# PAM8610.net
KiCad netlist of a schematic drawn in Altium Designer
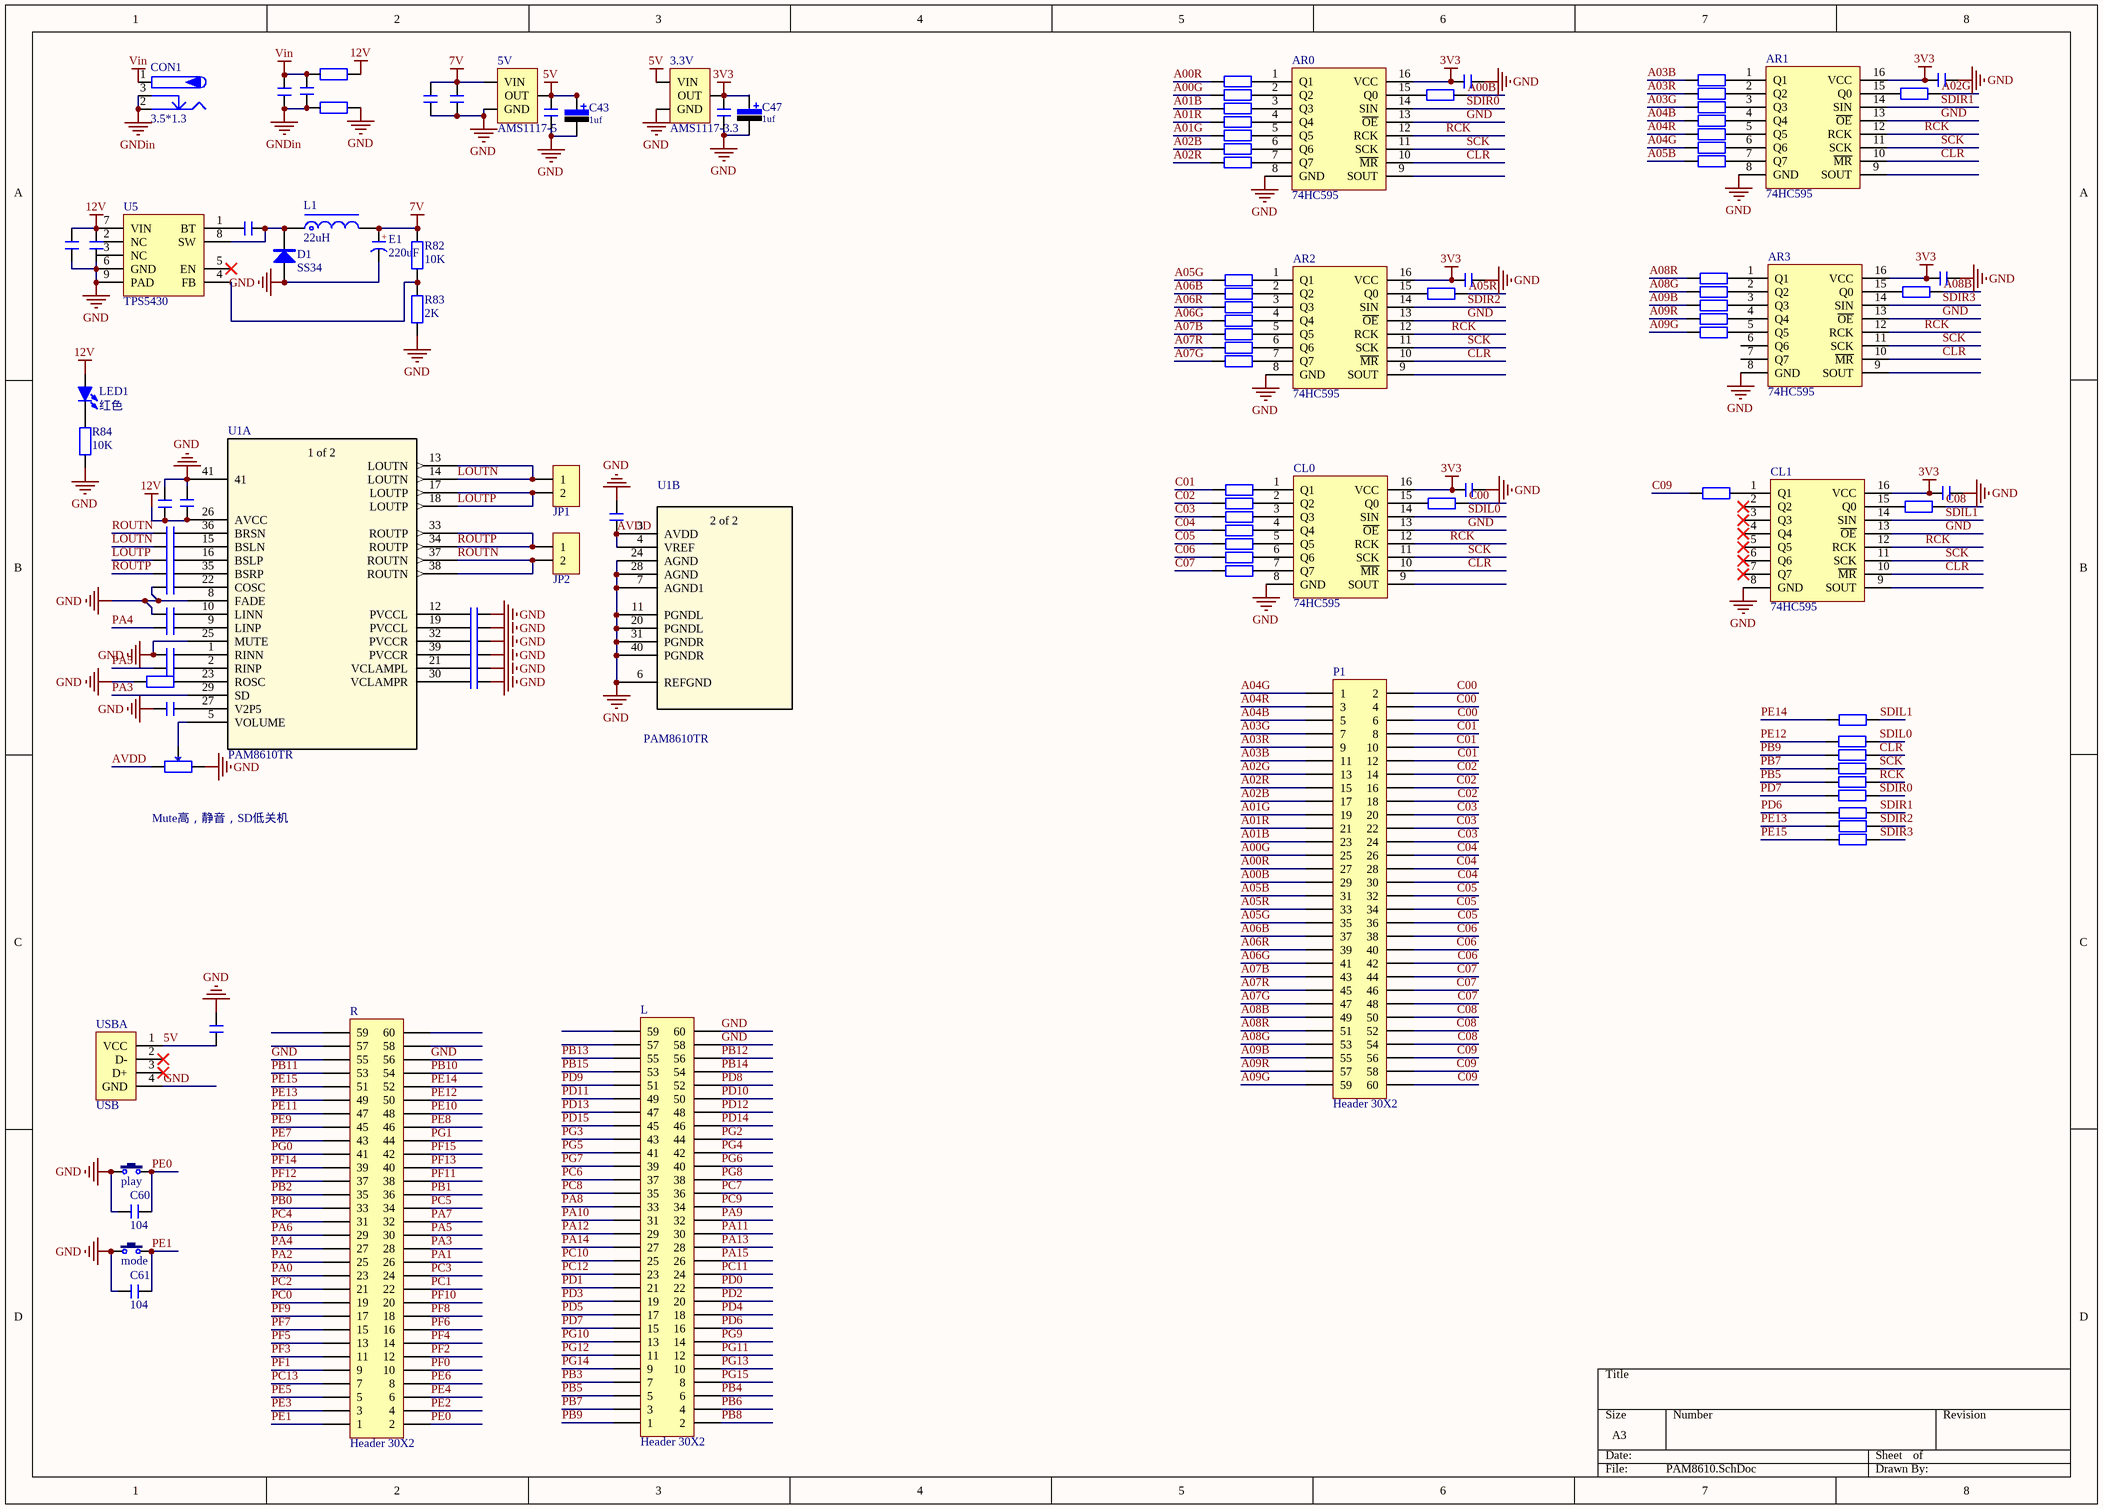
[diagram p0: PAM8610.SchDoc]

(export (version "E")
  (design (tool "Eeschema 10.0.6"))
  (components
    (comp (ref "3.3V")
      (value "AMS1117-3.3")
      (footprint "SOT-223")
      (libsource (lib "Library") (part "AMS1117"))
    )
    (comp (ref "5V") (value "AMS1117-5") (footprint "SOT-223") (libsource (lib "Library") (part "AMS1117")))
    (comp (ref "AR0")
      (value "74HC595")
      (footprint "TSSOP16_M")
      (description "8位移位寄存器")
      (fields (field (name "版权归属") "源创客"))
      (libsource (lib "IL") (part "74HC595"))
    )
    (comp (ref "AR1")
      (value "74HC595")
      (footprint "TSSOP16_M")
      (description "8位移位寄存器")
      (fields (field (name "版权归属") "源创客"))
      (libsource (lib "IL") (part "74HC595"))
    )
    (comp (ref "AR2")
      (value "74HC595")
      (footprint "TSSOP16_M")
      (description "8位移位寄存器")
      (fields (field (name "版权归属") "源创客"))
      (libsource (lib "IL") (part "74HC595"))
    )
    (comp (ref "AR3")
      (value "74HC595")
      (footprint "TSSOP16_M")
      (description "8位移位寄存器")
      (fields (field (name "版权归属") "源创客"))
      (libsource (lib "IL") (part "74HC595"))
    )
    (comp (ref "C4")
      (value "105")
      (footprint "C 0603_L")
      (description "无极性贴片电容")
      (fields (field (name "版权归属") "源创客"))
      (libsource (lib "IL") (part "C"))
    )
    (comp (ref "C5")
      (value "105")
      (footprint "C 0603_L")
      (description "无极性贴片电容")
      (fields (field (name "版权归属") "源创客"))
      (libsource (lib "IL") (part "C"))
    )
    (comp (ref "C6")
      (value "105")
      (footprint "C 0603_L")
      (description "无极性贴片电容")
      (fields (field (name "版权归属") "源创客"))
      (libsource (lib "IL") (part "C"))
    )
    (comp (ref "C7")
      (value "105")
      (footprint "C 0603_L")
      (description "无极性贴片电容")
      (fields (field (name "版权归属") "源创客"))
      (libsource (lib "IL") (part "C"))
    )
    (comp (ref "C9")
      (value "105")
      (footprint "C 0603_L")
      (description "无极性贴片电容")
      (fields (field (name "版权归属") "源创客"))
      (libsource (lib "IL") (part "C"))
    )
    (comp (ref "C10")
      (value "105")
      (footprint "C 0603_L")
      (description "无极性贴片电容")
      (fields (field (name "版权归属") "源创客"))
      (libsource (lib "IL") (part "C"))
    )
    (comp (ref "C15")
      (value "100nF")
      (footprint "C 0603_L")
      (description "无极性贴片电容")
      (fields (field (name "版权归属") "源创客"))
      (libsource (lib "IL") (part "C"))
    )
    (comp (ref "C16")
      (value "220pF")
      (footprint "C 0603_L")
      (description "无极性贴片电容")
      (fields (field (name "版权归属") "源创客"))
      (libsource (lib "IL") (part "C"))
    )
    (comp (ref "C17")
      (value "1uF")
      (footprint "C 0603_L")
      (description "无极性贴片电容")
      (fields (field (name "版权归属") "源创客"))
      (libsource (lib "IL") (part "C"))
    )
    (comp (ref "C18")
      (value "1uF")
      (footprint "C 0603_L")
      (description "无极性贴片电容")
      (fields (field (name "版权归属") "源创客"))
      (libsource (lib "IL") (part "C"))
    )
    (comp (ref "C19")
      (value "1uF")
      (footprint "C 0603_L")
      (description "无极性贴片电容")
      (fields (field (name "版权归属") "源创客"))
      (libsource (lib "IL") (part "C"))
    )
    (comp (ref "C20")
      (value "1uF")
      (footprint "C 0603_L")
      (description "无极性贴片电容")
      (fields (field (name "版权归属") "源创客"))
      (libsource (lib "IL") (part "C"))
    )
    (comp (ref "C21")
      (value "1uF")
      (footprint "C 0603_L")
      (description "无极性贴片电容")
      (fields (field (name "版权归属") "源创客"))
      (libsource (lib "IL") (part "C"))
    )
    (comp (ref "C23")
      (value "10uF")
      (footprint "C 0603_L")
      (description "无极性贴片电容")
      (fields (field (name "版权归属") "源创客"))
      (libsource (lib "IL") (part "C"))
    )
    (comp (ref "C24")
      (value "1uF")
      (footprint "C 0603_L")
      (description "无极性贴片电容")
      (fields (field (name "版权归属") "源创客"))
      (libsource (lib "IL") (part "C"))
    )
    (comp (ref "C25")
      (value "1uF")
      (footprint "C 0603_L")
      (description "无极性贴片电容")
      (fields (field (name "版权归属") "源创客"))
      (libsource (lib "IL") (part "C"))
    )
    (comp (ref "C26")
      (value "1uF")
      (footprint "C 0603_L")
      (description "无极性贴片电容")
      (fields (field (name "版权归属") "源创客"))
      (libsource (lib "IL") (part "C"))
    )
    (comp (ref "C27")
      (value "1uF")
      (footprint "C 0603_L")
      (description "无极性贴片电容")
      (fields (field (name "版权归属") "源创客"))
      (libsource (lib "IL") (part "C"))
    )
    (comp (ref "C28")
      (value "1uF")
      (footprint "C 0603_L")
      (description "无极性贴片电容")
      (fields (field (name "版权归属") "源创客"))
      (libsource (lib "IL") (part "C"))
    )
    (comp (ref "C29")
      (value "1uF")
      (footprint "C 0603_L")
      (description "无极性贴片电容")
      (fields (field (name "版权归属") "源创客"))
      (libsource (lib "IL") (part "C"))
    )
    (comp (ref "C30")
      (value "1uF")
      (footprint "C 0603_L")
      (description "无极性贴片电容")
      (fields (field (name "版权归属") "源创客"))
      (libsource (lib "IL") (part "C"))
    )
    (comp (ref "C31")
      (value "1uF")
      (footprint "C 0603_L")
      (description "无极性贴片电容")
      (fields (field (name "版权归属") "源创客"))
      (libsource (lib "IL") (part "C"))
    )
    (comp (ref "C32")
      (value "1uF")
      (footprint "C 0603_L")
      (description "无极性贴片电容")
      (fields (field (name "版权归属") "源创客"))
      (libsource (lib "IL") (part "C"))
    )
    (comp (ref "C33")
      (value "1uF")
      (footprint "C 0603_L")
      (description "无极性贴片电容")
      (fields (field (name "版权归属") "源创客"))
      (libsource (lib "IL") (part "C"))
    )
    (comp (ref "C34")
      (value "1uF")
      (footprint "C 0603_L")
      (description "无极性贴片电容")
      (fields (field (name "版权归属") "源创客"))
      (libsource (lib "IL") (part "C"))
    )
    (comp (ref "C36")
      (value "10uF")
      (footprint "C 0603_L")
      (description "无极性贴片电容")
      (fields (field (name "版权归属") "源创客"))
      (libsource (lib "IL") (part "C"))
    )
    (comp (ref "C37")
      (value "100nF")
      (footprint "C 0603_L")
      (description "无极性贴片电容")
      (fields (field (name "版权归属") "源创客"))
      (libsource (lib "IL") (part "C"))
    )
    (comp (ref "C40")
      (value "100nF")
      (footprint "C 0603_L")
      (description "无极性贴片电容")
      (fields (field (name "版权归属") "源创客"))
      (libsource (lib "IL") (part "C"))
    )
    (comp (ref "C41")
      (value "10uF")
      (footprint "C 0603_L")
      (description "无极性贴片电容")
      (fields (field (name "版权归属") "源创客"))
      (libsource (lib "IL") (part "C"))
    )
    (comp (ref "C42")
      (value "100nF")
      (footprint "C 0603_L")
      (description "无极性贴片电容")
      (fields (field (name "版权归属") "源创客"))
      (libsource (lib "IL") (part "C"))
    )
    (comp (ref "C43")
      (value "1uf")
      (footprint "C-AVX-3528")
      (description "极性钽电容")
      (fields (field (name "Comment") "C"))
      (libsource (lib "Library") (part "Cap-Ta"))
    )
    (comp (ref "C46")
      (value "100nF")
      (footprint "C 0603_L")
      (description "无极性贴片电容")
      (fields (field (name "版权归属") "源创客"))
      (libsource (lib "IL") (part "C"))
    )
    (comp (ref "C47")
      (value "1uf")
      (footprint "C-AVX-3528")
      (description "极性钽电容")
      (fields (field (name "Comment") "C"))
      (libsource (lib "Library") (part "Cap-Ta"))
    )
    (comp (ref "C51")
      (value "10uF")
      (footprint "C 0603_L")
      (description "无极性贴片电容")
      (fields (field (name "版权归属") "源创客"))
      (libsource (lib "IL") (part "C"))
    )
    (comp (ref "C52")
      (value "100nF")
      (footprint "C 0603_L")
      (description "无极性贴片电容")
      (fields (field (name "版权归属") "源创客"))
      (libsource (lib "IL") (part "C"))
    )
    (comp (ref "C53")
      (value "10nF")
      (footprint "C 0603_L")
      (description "无极性贴片电容")
      (fields (field (name "版权归属") "源创客"))
      (libsource (lib "IL") (part "C"))
    )
    (comp (ref "C59")
      (value "100nF")
      (footprint "C 0603_L")
      (description "无极性贴片电容")
      (fields (field (name "版权归属") "源创客"))
      (libsource (lib "IL") (part "C"))
    )
    (comp (ref "C60")
      (value "104")
      (footprint "C 0603_L")
      (description "无极性贴片电容")
      (fields (field (name "版权归属") "源创客"))
      (libsource (lib "IL") (part "C"))
    )
    (comp (ref "C61")
      (value "104")
      (footprint "C 0603_L")
      (description "无极性贴片电容")
      (fields (field (name "版权归属") "源创客"))
      (libsource (lib "IL") (part "C"))
    )
    (comp (ref "CL0")
      (value "74HC595")
      (footprint "TSSOP16_M")
      (description "8位移位寄存器")
      (fields (field (name "版权归属") "源创客"))
      (libsource (lib "IL") (part "74HC595"))
    )
    (comp (ref "CL1")
      (value "74HC595")
      (footprint "TSSOP16_M")
      (description "8位移位寄存器")
      (fields (field (name "版权归属") "源创客"))
      (libsource (lib "IL") (part "74HC595"))
    )
    (comp (ref "CON1")
      (value "3.5*1.3")
      (footprint "DC-005")
      (description "低压电源接口")
      (fields (field (name "版权归属") "源创客"))
      (libsource (lib "IL") (part "P-DC"))
    )
    (comp (ref "D1")
      (value "SS34")
      (footprint "SMA")
      (description "肖特基二极管")
      (fields (field (name "版权归属") "源创客"))
      (libsource (lib "IL") (part "SS34"))
    )
    (comp (ref "E1")
      (value "220uF")
      (footprint "CT 8*7 - C")
      (description "贴片固态电容")
      (fields (field (name "版权归属") "源创客"))
      (libsource (lib "IL") (part "C-CT"))
    )
    (comp (ref "FB1")
      (value "600R")
      (footprint "FB-0805")
      (description "磁珠")
      (libsource (lib "Library") (part "FB"))
    )
    (comp (ref "FB2")
      (value "600R")
      (footprint "FB-0805")
      (description "磁珠")
      (libsource (lib "Library") (part "FB"))
    )
    (comp (ref "JP1")
      (value "HDR-1X2")
      (footprint "HDR2.54-LI-2P")
      (description "2P接插件")
      (fields (field (name "版权归属") "源创客"))
      (libsource (lib "IL") (part "Header 2"))
    )
    (comp (ref "JP2")
      (value "HDR-1X2")
      (footprint "HDR2.54-LI-2P")
      (description "2P接插件")
      (fields (field (name "版权归属") "源创客"))
      (libsource (lib "IL") (part "Header 2"))
    )
    (comp (ref "L")
      (value "Header 30X2")
      (footprint "HDR2X30")
      (description "Header, 30-Pin, Dual row")
      (fields (field (name "PUBLISHER") "Altium Limited"))
      (libsource (lib "Miscellaneous Connectors") (part "Header 30X2"))
    )
    (comp (ref "L1")
      (value "22uH")
      (footprint "CDRH74")
      (description "功率屏蔽电感")
      (fields (field (name "版权归属") "源创客"))
      (libsource (lib "IL") (part "L-CDRH"))
    )
    (comp (ref "LED1")
      (value "红色")
      (footprint "LED 0603B")
      (description "贴片LED")
      (fields (field (name "版权归属") "源创客"))
      (libsource (lib "IL") (part "LED-SMD"))
    )
    (comp (ref "mode")
      (value "3x6x5")
      (footprint "TSW SMD-3*6*2.5")
      (description "3x6轻触开关")
      (fields (field (name "版权归属") "源创客"))
      (libsource (lib "IL") (part "TSW 3x6"))
    )
    (comp (ref "P1")
      (value "Header 30X2")
      (footprint "HDR2X30")
      (description "Header, 30-Pin, Dual row")
      (fields (field (name "PUBLISHER") "Altium Limited"))
      (libsource (lib "") (part "Header 30X2_1"))
    )
    (comp (ref "play")
      (value "3x6x5")
      (footprint "TSW SMD-3*6*2.5")
      (description "3x6轻触开关")
      (fields (field (name "版权归属") "源创客"))
      (libsource (lib "IL") (part "TSW 3x6"))
    )
    (comp (ref "R")
      (value "Header 30X2")
      (footprint "HDR2X30")
      (description "Header, 30-Pin, Dual row")
      (fields (field (name "PUBLISHER") "Altium Limited"))
      (libsource (lib "Miscellaneous Connectors") (part "Header 30X2"))
    )
    (comp (ref "R0")
      (value "220")
      (footprint "R 0603_L")
      (description "贴片电阻")
      (fields (field (name "版权归属") "源创客"))
      (libsource (lib "IL") (part "R"))
    )
    (comp (ref "R1")
      (value "220")
      (footprint "R 0603_L")
      (description "贴片电阻")
      (fields (field (name "版权归属") "源创客"))
      (libsource (lib "IL") (part "R"))
    )
    (comp (ref "R2")
      (value "220")
      (footprint "R 0603_L")
      (description "贴片电阻")
      (fields (field (name "版权归属") "源创客"))
      (libsource (lib "IL") (part "R"))
    )
    (comp (ref "R3")
      (value "220")
      (footprint "R 0603_L")
      (description "贴片电阻")
      (fields (field (name "版权归属") "源创客"))
      (libsource (lib "IL") (part "R"))
    )
    (comp (ref "R4")
      (value "220")
      (footprint "R 0603_L")
      (description "贴片电阻")
      (fields (field (name "版权归属") "源创客"))
      (libsource (lib "IL") (part "R"))
    )
    (comp (ref "R5")
      (value "220")
      (footprint "R 0603_L")
      (description "贴片电阻")
      (fields (field (name "版权归属") "源创客"))
      (libsource (lib "IL") (part "R"))
    )
    (comp (ref "R6")
      (value "220")
      (footprint "R 0603_L")
      (description "贴片电阻")
      (fields (field (name "版权归属") "源创客"))
      (libsource (lib "IL") (part "R"))
    )
    (comp (ref "R7")
      (value "220")
      (footprint "R 0603_L")
      (description "贴片电阻")
      (fields (field (name "版权归属") "源创客"))
      (libsource (lib "IL") (part "R"))
    )
    (comp (ref "R8")
      (value "220")
      (footprint "R 0603_L")
      (description "贴片电阻")
      (fields (field (name "版权归属") "源创客"))
      (libsource (lib "IL") (part "R"))
    )
    (comp (ref "R9")
      (value "220")
      (footprint "R 0603_L")
      (description "贴片电阻")
      (fields (field (name "版权归属") "源创客"))
      (libsource (lib "IL") (part "R"))
    )
    (comp (ref "R10")
      (value "220")
      (footprint "R 0603_L")
      (description "贴片电阻")
      (fields (field (name "版权归属") "源创客"))
      (libsource (lib "IL") (part "R"))
    )
    (comp (ref "R11")
      (value "220")
      (footprint "R 0603_L")
      (description "贴片电阻")
      (fields (field (name "版权归属") "源创客"))
      (libsource (lib "IL") (part "R"))
    )
    (comp (ref "R12")
      (value "220")
      (footprint "R 0603_L")
      (description "贴片电阻")
      (fields (field (name "版权归属") "源创客"))
      (libsource (lib "IL") (part "R"))
    )
    (comp (ref "R13")
      (value "220")
      (footprint "R 0603_L")
      (description "贴片电阻")
      (fields (field (name "版权归属") "源创客"))
      (libsource (lib "IL") (part "R"))
    )
    (comp (ref "R14")
      (value "220")
      (footprint "R 0603_L")
      (description "贴片电阻")
      (fields (field (name "版权归属") "源创客"))
      (libsource (lib "IL") (part "R"))
    )
    (comp (ref "R15")
      (value "220")
      (footprint "R 0603_L")
      (description "贴片电阻")
      (fields (field (name "版权归属") "源创客"))
      (libsource (lib "IL") (part "R"))
    )
    (comp (ref "R16")
      (value "220")
      (footprint "R 0603_L")
      (description "贴片电阻")
      (fields (field (name "版权归属") "源创客"))
      (libsource (lib "IL") (part "R"))
    )
    (comp (ref "R17")
      (value "220")
      (footprint "R 0603_L")
      (description "贴片电阻")
      (fields (field (name "版权归属") "源创客"))
      (libsource (lib "IL") (part "R"))
    )
    (comp (ref "R18")
      (value "220")
      (footprint "R 0603_L")
      (description "贴片电阻")
      (fields (field (name "版权归属") "源创客"))
      (libsource (lib "IL") (part "R"))
    )
    (comp (ref "R19")
      (value "220")
      (footprint "R 0603_L")
      (description "贴片电阻")
      (fields (field (name "版权归属") "源创客"))
      (libsource (lib "IL") (part "R"))
    )
    (comp (ref "R20")
      (value "220")
      (footprint "R 0603_L")
      (description "贴片电阻")
      (fields (field (name "版权归属") "源创客"))
      (libsource (lib "IL") (part "R"))
    )
    (comp (ref "R21")
      (value "220")
      (footprint "R 0603_L")
      (description "贴片电阻")
      (fields (field (name "版权归属") "源创客"))
      (libsource (lib "IL") (part "R"))
    )
    (comp (ref "R22")
      (value "220")
      (footprint "R 0603_L")
      (description "贴片电阻")
      (fields (field (name "版权归属") "源创客"))
      (libsource (lib "IL") (part "R"))
    )
    (comp (ref "R23")
      (value "220")
      (footprint "R 0603_L")
      (description "贴片电阻")
      (fields (field (name "版权归属") "源创客"))
      (libsource (lib "IL") (part "R"))
    )
    (comp (ref "R24")
      (value "220")
      (footprint "R 0603_L")
      (description "贴片电阻")
      (fields (field (name "版权归属") "源创客"))
      (libsource (lib "IL") (part "R"))
    )
    (comp (ref "R25")
      (value "220")
      (footprint "R 0603_L")
      (description "贴片电阻")
      (fields (field (name "版权归属") "源创客"))
      (libsource (lib "IL") (part "R"))
    )
    (comp (ref "R26")
      (value "220")
      (footprint "R 0603_L")
      (description "贴片电阻")
      (fields (field (name "版权归属") "源创客"))
      (libsource (lib "IL") (part "R"))
    )
    (comp (ref "R27")
      (value "220")
      (footprint "R 0603_L")
      (description "贴片电阻")
      (fields (field (name "版权归属") "源创客"))
      (libsource (lib "IL") (part "R"))
    )
    (comp (ref "R28")
      (value "220")
      (footprint "R 0603_L")
      (description "贴片电阻")
      (fields (field (name "版权归属") "源创客"))
      (libsource (lib "IL") (part "R"))
    )
    (comp (ref "R29")
      (value "220")
      (footprint "R 0603_L")
      (description "贴片电阻")
      (fields (field (name "版权归属") "源创客"))
      (libsource (lib "IL") (part "R"))
    )
    (comp (ref "R40")
      (value "220")
      (footprint "R 0603_L")
      (description "贴片电阻")
      (fields (field (name "版权归属") "源创客"))
      (libsource (lib "IL") (part "R"))
    )
    (comp (ref "R41")
      (value "220")
      (footprint "R 0603_L")
      (description "贴片电阻")
      (fields (field (name "版权归属") "源创客"))
      (libsource (lib "IL") (part "R"))
    )
    (comp (ref "R42")
      (value "220")
      (footprint "R 0603_L")
      (description "贴片电阻")
      (fields (field (name "版权归属") "源创客"))
      (libsource (lib "IL") (part "R"))
    )
    (comp (ref "R43")
      (value "220")
      (footprint "R 0603_L")
      (description "贴片电阻")
      (fields (field (name "版权归属") "源创客"))
      (libsource (lib "IL") (part "R"))
    )
    (comp (ref "R44")
      (value "220")
      (footprint "R 0603_L")
      (description "贴片电阻")
      (fields (field (name "版权归属") "源创客"))
      (libsource (lib "IL") (part "R"))
    )
    (comp (ref "R45")
      (value "220")
      (footprint "R 0603_L")
      (description "贴片电阻")
      (fields (field (name "版权归属") "源创客"))
      (libsource (lib "IL") (part "R"))
    )
    (comp (ref "R46")
      (value "220")
      (footprint "R 0603_L")
      (description "贴片电阻")
      (fields (field (name "版权归属") "源创客"))
      (libsource (lib "IL") (part "R"))
    )
    (comp (ref "R47")
      (value "220")
      (footprint "R 0603_L")
      (description "贴片电阻")
      (fields (field (name "版权归属") "源创客"))
      (libsource (lib "IL") (part "R"))
    )
    (comp (ref "R48")
      (value "220")
      (footprint "R 0603_L")
      (description "贴片电阻")
      (fields (field (name "版权归属") "源创客"))
      (libsource (lib "IL") (part "R"))
    )
    (comp (ref "R49")
      (value "220")
      (footprint "R 0603_L")
      (description "贴片电阻")
      (fields (field (name "版权归属") "源创客"))
      (libsource (lib "IL") (part "R"))
    )
    (comp (ref "R72")
      (value "120K")
      (footprint "R 0603_L")
      (description "贴片电阻")
      (fields (field (name "版权归属") "源创客"))
      (libsource (lib "IL") (part "R"))
    )
    (comp (ref "R82")
      (value "10K")
      (footprint "R 0603_L")
      (description "贴片电阻")
      (fields (field (name "版权归属") "源创客"))
      (libsource (lib "IL") (part "R"))
    )
    (comp (ref "R83")
      (value "2K")
      (footprint "R 0603_L")
      (description "贴片电阻")
      (fields (field (name "版权归属") "源创客"))
      (libsource (lib "IL") (part "R"))
    )
    (comp (ref "R84")
      (value "10K")
      (footprint "R 0603_L")
      (description "贴片电阻")
      (fields (field (name "版权归属") "源创客"))
      (libsource (lib "IL") (part "R"))
    )
    (comp (ref "R143")
      (value "47")
      (footprint "R 0603_L")
      (description "贴片电阻")
      (fields (field (name "版权归属") "源创客"))
      (libsource (lib "IL") (part "R"))
    )
    (comp (ref "R144")
      (value "47")
      (footprint "R 0603_L")
      (description "贴片电阻")
      (fields (field (name "版权归属") "源创客"))
      (libsource (lib "IL") (part "R"))
    )
    (comp (ref "R145")
      (value "47")
      (footprint "R 0603_L")
      (description "贴片电阻")
      (fields (field (name "版权归属") "源创客"))
      (libsource (lib "IL") (part "R"))
    )
    (comp (ref "R146")
      (value "47")
      (footprint "R 0603_L")
      (description "贴片电阻")
      (fields (field (name "版权归属") "源创客"))
      (libsource (lib "IL") (part "R"))
    )
    (comp (ref "R147")
      (value "47")
      (footprint "R 0603_L")
      (description "贴片电阻")
      (fields (field (name "版权归属") "源创客"))
      (libsource (lib "IL") (part "R"))
    )
    (comp (ref "R148")
      (value "47")
      (footprint "R 0603_L")
      (description "贴片电阻")
      (fields (field (name "版权归属") "源创客"))
      (libsource (lib "IL") (part "R"))
    )
    (comp (ref "R149")
      (value "47")
      (footprint "R 0603_L")
      (description "贴片电阻")
      (fields (field (name "版权归属") "源创客"))
      (libsource (lib "IL") (part "R"))
    )
    (comp (ref "R150")
      (value "47")
      (footprint "R 0603_L")
      (description "贴片电阻")
      (fields (field (name "版权归属") "源创客"))
      (libsource (lib "IL") (part "R"))
    )
    (comp (ref "R151")
      (value "47")
      (footprint "R 0603_L")
      (description "贴片电阻")
      (fields (field (name "版权归属") "源创客"))
      (libsource (lib "IL") (part "R"))
    )
    (comp (ref "RP1")
      (value "200K")
      (footprint "3362P")
      (description "插件单联电位器")
      (fields (field (name "版权归属") "源创客"))
      (libsource (lib "IL") (part "RP-ID"))
    )
    (comp (ref "U1")
      (value "PAM8610TR")
      (footprint "QFN_610TR_DIO")
      (description "D类功放")
      (fields (field (name "COPYRIGHT") "Copyright (C) 2021 Ultra Librarian. All rights reserved."))
      (libsource (lib "") (part "PAM8610TR_1_1"))
    )
    (comp (ref "U5")
      (value "TPS5430")
      (footprint "SOP-8 with pad")
      (libsource (lib "Library") (part "TPS5430"))
    )
    (comp (ref "USBA")
      (value "USB")
      (footprint "USB-A/S_B")
      (description "USB-A型母接口")
      (fields (field (name "版权归属") "源创客"))
      (libsource (lib "IL") (part "USB-A/S"))
    )
  )
  (nets
    (net (code "2") (name "/A00B") (class "Default")
      (node (ref "P1") (pin "29") (pinfunction "29_29") (pintype "passive"))
      (node (ref "R0") (pin "2") (pinfunction "2_2") (pintype "passive"))
    )
    (net (code "3") (name "/A00G") (class "Default")
      (node (ref "P1") (pin "25") (pinfunction "25_25") (pintype "passive"))
      (node (ref "R2") (pin "1") (pinfunction "1_1") (pintype "passive"))
    )
    (net (code "4") (name "/A00R") (class "Default")
      (node (ref "P1") (pin "27") (pinfunction "27_27") (pintype "passive"))
      (node (ref "R1") (pin "1") (pinfunction "1_1") (pintype "passive"))
    )
    (net (code "5") (name "/A01B") (class "Default")
      (node (ref "P1") (pin "23") (pinfunction "23_23") (pintype "passive"))
      (node (ref "R3") (pin "1") (pinfunction "1_1") (pintype "passive"))
    )
    (net (code "6") (name "/A01G") (class "Default")
      (node (ref "P1") (pin "19") (pinfunction "19_19") (pintype "passive"))
      (node (ref "R5") (pin "1") (pinfunction "1_1") (pintype "passive"))
    )
    (net (code "7") (name "/A01R") (class "Default")
      (node (ref "P1") (pin "21") (pinfunction "21_21") (pintype "passive"))
      (node (ref "R4") (pin "1") (pinfunction "1_1") (pintype "passive"))
    )
    (net (code "8") (name "/A02B") (class "Default")
      (node (ref "P1") (pin "17") (pinfunction "17_17") (pintype "passive"))
      (node (ref "R6") (pin "1") (pinfunction "1_1") (pintype "passive"))
    )
    (net (code "9") (name "/A02G") (class "Default")
      (node (ref "P1") (pin "13") (pinfunction "13_13") (pintype "passive"))
      (node (ref "R8") (pin "2") (pinfunction "2_2") (pintype "passive"))
    )
    (net (code "10") (name "/A02R") (class "Default")
      (node (ref "P1") (pin "15") (pinfunction "15_15") (pintype "passive"))
      (node (ref "R7") (pin "1") (pinfunction "1_1") (pintype "passive"))
    )
    (net (code "11") (name "/A03B") (class "Default")
      (node (ref "P1") (pin "11") (pinfunction "11_11") (pintype "passive"))
      (node (ref "R9") (pin "1") (pinfunction "1_1") (pintype "passive"))
    )
    (net (code "12") (name "/A03G") (class "Default")
      (node (ref "P1") (pin "7") (pinfunction "7_7") (pintype "passive"))
      (node (ref "R11") (pin "1") (pinfunction "1_1") (pintype "passive"))
    )
    (net (code "13") (name "/A03R") (class "Default")
      (node (ref "P1") (pin "9") (pinfunction "9_9") (pintype "passive"))
      (node (ref "R10") (pin "1") (pinfunction "1_1") (pintype "passive"))
    )
    (net (code "14") (name "/A04B") (class "Default")
      (node (ref "P1") (pin "5") (pinfunction "5_5") (pintype "passive"))
      (node (ref "R12") (pin "1") (pinfunction "1_1") (pintype "passive"))
    )
    (net (code "15") (name "/A04G") (class "Default")
      (node (ref "P1") (pin "1") (pinfunction "1_1") (pintype "passive"))
      (node (ref "R14") (pin "1") (pinfunction "1_1") (pintype "passive"))
    )
    (net (code "16") (name "/A04R") (class "Default")
      (node (ref "P1") (pin "3") (pinfunction "3_3") (pintype "passive"))
      (node (ref "R13") (pin "1") (pinfunction "1_1") (pintype "passive"))
    )
    (net (code "17") (name "/A05B") (class "Default")
      (node (ref "P1") (pin "31") (pinfunction "31_31") (pintype "passive"))
      (node (ref "R15") (pin "1") (pinfunction "1_1") (pintype "passive"))
    )
    (net (code "18") (name "/A05G") (class "Default")
      (node (ref "P1") (pin "35") (pinfunction "35_35") (pintype "passive"))
      (node (ref "R17") (pin "1") (pinfunction "1_1") (pintype "passive"))
    )
    (net (code "19") (name "/A05R") (class "Default")
      (node (ref "P1") (pin "33") (pinfunction "33_33") (pintype "passive"))
      (node (ref "R16") (pin "2") (pinfunction "2_2") (pintype "passive"))
    )
    (net (code "20") (name "/A06B") (class "Default")
      (node (ref "P1") (pin "37") (pinfunction "37_37") (pintype "passive"))
      (node (ref "R18") (pin "1") (pinfunction "1_1") (pintype "passive"))
    )
    (net (code "21") (name "/A06G") (class "Default")
      (node (ref "P1") (pin "41") (pinfunction "41_41") (pintype "passive"))
      (node (ref "R20") (pin "1") (pinfunction "1_1") (pintype "passive"))
    )
    (net (code "22") (name "/A06R") (class "Default")
      (node (ref "P1") (pin "39") (pinfunction "39_39") (pintype "passive"))
      (node (ref "R19") (pin "1") (pinfunction "1_1") (pintype "passive"))
    )
    (net (code "23") (name "/A07B") (class "Default")
      (node (ref "P1") (pin "43") (pinfunction "43_43") (pintype "passive"))
      (node (ref "R21") (pin "1") (pinfunction "1_1") (pintype "passive"))
    )
    (net (code "24") (name "/A07G") (class "Default")
      (node (ref "P1") (pin "47") (pinfunction "47_47") (pintype "passive"))
      (node (ref "R23") (pin "1") (pinfunction "1_1") (pintype "passive"))
    )
    (net (code "25") (name "/A07R") (class "Default")
      (node (ref "P1") (pin "45") (pinfunction "45_45") (pintype "passive"))
      (node (ref "R22") (pin "1") (pinfunction "1_1") (pintype "passive"))
    )
    (net (code "26") (name "/A08B") (class "Default")
      (node (ref "P1") (pin "49") (pinfunction "49_49") (pintype "passive"))
      (node (ref "R24") (pin "2") (pinfunction "2_2") (pintype "passive"))
    )
    (net (code "27") (name "/A08G") (class "Default")
      (node (ref "P1") (pin "53") (pinfunction "53_53") (pintype "passive"))
      (node (ref "R26") (pin "1") (pinfunction "1_1") (pintype "passive"))
    )
    (net (code "28") (name "/A08R") (class "Default")
      (node (ref "P1") (pin "51") (pinfunction "51_51") (pintype "passive"))
      (node (ref "R25") (pin "1") (pinfunction "1_1") (pintype "passive"))
    )
    (net (code "29") (name "/A09B") (class "Default")
      (node (ref "P1") (pin "55") (pinfunction "55_55") (pintype "passive"))
      (node (ref "R27") (pin "1") (pinfunction "1_1") (pintype "passive"))
    )
    (net (code "30") (name "/A09G") (class "Default")
      (node (ref "P1") (pin "59") (pinfunction "59_59") (pintype "passive"))
      (node (ref "R29") (pin "1") (pinfunction "1_1") (pintype "passive"))
    )
    (net (code "31") (name "/A09R") (class "Default")
      (node (ref "P1") (pin "57") (pinfunction "57_57") (pintype "passive"))
      (node (ref "R28") (pin "1") (pinfunction "1_1") (pintype "passive"))
    )
    (net (code "32") (name "/AVDD") (class "Default")
      (node (ref "C24") (pin "1") (pinfunction "1_1") (pintype "passive"))
      (node (ref "RP1") (pin "1") (pinfunction "1_1") (pintype "passive"))
      (node (ref "U1") (pin "3") (pinfunction "AVDD_3") (pintype "power_in"))
      (node (ref "U1") (pin "4") (pinfunction "VREF_4") (pintype "power_in"))
    )
    (net (code "33") (name "/C00") (class "Default")
      (node (ref "P1") (pin "2") (pinfunction "2_2") (pintype "passive"))
      (node (ref "P1") (pin "4") (pinfunction "4_4") (pintype "passive"))
      (node (ref "P1") (pin "6") (pinfunction "6_6") (pintype "passive"))
      (node (ref "R40") (pin "2") (pinfunction "2_2") (pintype "passive"))
    )
    (net (code "34") (name "/C01") (class "Default")
      (node (ref "P1") (pin "10") (pinfunction "10_10") (pintype "passive"))
      (node (ref "P1") (pin "12") (pinfunction "12_12") (pintype "passive"))
      (node (ref "P1") (pin "8") (pinfunction "8_8") (pintype "passive"))
      (node (ref "R41") (pin "1") (pinfunction "1_1") (pintype "passive"))
    )
    (net (code "35") (name "/C02") (class "Default")
      (node (ref "P1") (pin "14") (pinfunction "14_14") (pintype "passive"))
      (node (ref "P1") (pin "16") (pinfunction "16_16") (pintype "passive"))
      (node (ref "P1") (pin "18") (pinfunction "18_18") (pintype "passive"))
      (node (ref "R42") (pin "1") (pinfunction "1_1") (pintype "passive"))
    )
    (net (code "36") (name "/C03") (class "Default")
      (node (ref "P1") (pin "20") (pinfunction "20_20") (pintype "passive"))
      (node (ref "P1") (pin "22") (pinfunction "22_22") (pintype "passive"))
      (node (ref "P1") (pin "24") (pinfunction "24_24") (pintype "passive"))
      (node (ref "R43") (pin "1") (pinfunction "1_1") (pintype "passive"))
    )
    (net (code "37") (name "/C04") (class "Default")
      (node (ref "P1") (pin "26") (pinfunction "26_26") (pintype "passive"))
      (node (ref "P1") (pin "28") (pinfunction "28_28") (pintype "passive"))
      (node (ref "P1") (pin "30") (pinfunction "30_30") (pintype "passive"))
      (node (ref "R44") (pin "1") (pinfunction "1_1") (pintype "passive"))
    )
    (net (code "38") (name "/C05") (class "Default")
      (node (ref "P1") (pin "32") (pinfunction "32_32") (pintype "passive"))
      (node (ref "P1") (pin "34") (pinfunction "34_34") (pintype "passive"))
      (node (ref "P1") (pin "36") (pinfunction "36_36") (pintype "passive"))
      (node (ref "R45") (pin "1") (pinfunction "1_1") (pintype "passive"))
    )
    (net (code "39") (name "/C06") (class "Default")
      (node (ref "P1") (pin "38") (pinfunction "38_38") (pintype "passive"))
      (node (ref "P1") (pin "40") (pinfunction "40_40") (pintype "passive"))
      (node (ref "P1") (pin "42") (pinfunction "42_42") (pintype "passive"))
      (node (ref "R46") (pin "1") (pinfunction "1_1") (pintype "passive"))
    )
    (net (code "40") (name "/C07") (class "Default")
      (node (ref "P1") (pin "44") (pinfunction "44_44") (pintype "passive"))
      (node (ref "P1") (pin "46") (pinfunction "46_46") (pintype "passive"))
      (node (ref "P1") (pin "48") (pinfunction "48_48") (pintype "passive"))
      (node (ref "R47") (pin "1") (pinfunction "1_1") (pintype "passive"))
    )
    (net (code "41") (name "/C08") (class "Default")
      (node (ref "P1") (pin "50") (pinfunction "50_50") (pintype "passive"))
      (node (ref "P1") (pin "52") (pinfunction "52_52") (pintype "passive"))
      (node (ref "P1") (pin "54") (pinfunction "54_54") (pintype "passive"))
      (node (ref "R48") (pin "2") (pinfunction "2_2") (pintype "passive"))
    )
    (net (code "42") (name "/C09") (class "Default")
      (node (ref "P1") (pin "56") (pinfunction "56_56") (pintype "passive"))
      (node (ref "P1") (pin "58") (pinfunction "58_58") (pintype "passive"))
      (node (ref "P1") (pin "60") (pinfunction "60_60") (pintype "passive"))
      (node (ref "R49") (pin "1") (pinfunction "1_1") (pintype "passive"))
    )
    (net (code "43") (name "/CLR") (class "Default")
      (node (ref "AR0") (pin "10") (pinfunction "~{MR}_10") (pintype "passive"))
      (node (ref "AR1") (pin "10") (pinfunction "~{MR}_10") (pintype "passive"))
      (node (ref "AR2") (pin "10") (pinfunction "~{MR}_10") (pintype "passive"))
      (node (ref "AR3") (pin "10") (pinfunction "~{MR}_10") (pintype "passive"))
      (node (ref "CL0") (pin "10") (pinfunction "~{MR}_10") (pintype "passive"))
      (node (ref "CL1") (pin "10") (pinfunction "~{MR}_10") (pintype "passive"))
      (node (ref "R145") (pin "2") (pinfunction "2_2") (pintype "passive"))
    )
    (net (code "44") (name "/LOUTN") (class "Default")
      (node (ref "C27") (pin "2") (pinfunction "2_2") (pintype "passive"))
      (node (ref "JP1") (pin "1") (pinfunction "1_1") (pintype "passive"))
      (node (ref "U1") (pin "13") (pinfunction "LOUTN_13") (pintype "output"))
      (node (ref "U1") (pin "14") (pinfunction "LOUTN_14") (pintype "output"))
    )
    (net (code "45") (name "/LOUTP") (class "Default")
      (node (ref "C26") (pin "2") (pinfunction "2_2") (pintype "passive"))
      (node (ref "JP1") (pin "2") (pinfunction "2_2") (pintype "passive"))
      (node (ref "U1") (pin "17") (pinfunction "LOUTP_17") (pintype "output"))
      (node (ref "U1") (pin "18") (pinfunction "LOUTP_18") (pintype "output"))
    )
    (net (code "46") (name "/PA0") (class "Default")
      (node (ref "R") (pin "23") (pinfunction "23_23") (pintype "passive"))
    )
    (net (code "47") (name "/PA1") (class "Default")
      (node (ref "R") (pin "26") (pinfunction "26_26") (pintype "passive"))
    )
    (net (code "48") (name "/PA2") (class "Default")
      (node (ref "R") (pin "25") (pinfunction "25_25") (pintype "passive"))
    )
    (net (code "49") (name "/PA3") (class "Default")
      (node (ref "R") (pin "28") (pinfunction "28_28") (pintype "passive"))
      (node (ref "U1") (pin "29") (pinfunction "SD_29") (pintype "passive"))
    )
    (net (code "50") (name "/PA4") (class "Default")
      (node (ref "C18") (pin "1") (pinfunction "1_1") (pintype "passive"))
      (node (ref "R") (pin "27") (pinfunction "27_27") (pintype "passive"))
    )
    (net (code "51") (name "/PA5") (class "Default")
      (node (ref "C20") (pin "1") (pinfunction "1_1") (pintype "passive"))
      (node (ref "R") (pin "30") (pinfunction "30_30") (pintype "passive"))
    )
    (net (code "52") (name "/PA6") (class "Default")
      (node (ref "R") (pin "29") (pinfunction "29_29") (pintype "passive"))
    )
    (net (code "53") (name "/PA7") (class "Default")
      (node (ref "R") (pin "32") (pinfunction "32_32") (pintype "passive"))
    )
    (net (code "54") (name "/PA8") (class "Default")
      (node (ref "L") (pin "33") (pinfunction "33_33") (pintype "passive"))
    )
    (net (code "55") (name "/PA9") (class "Default")
      (node (ref "L") (pin "32") (pinfunction "32_32") (pintype "passive"))
    )
    (net (code "56") (name "/PA10") (class "Default")
      (node (ref "L") (pin "31") (pinfunction "31_31") (pintype "passive"))
    )
    (net (code "57") (name "/PA11") (class "Default")
      (node (ref "L") (pin "30") (pinfunction "30_30") (pintype "passive"))
    )
    (net (code "58") (name "/PA12") (class "Default")
      (node (ref "L") (pin "29") (pinfunction "29_29") (pintype "passive"))
    )
    (net (code "59") (name "/PA13") (class "Default")
      (node (ref "L") (pin "28") (pinfunction "28_28") (pintype "passive"))
    )
    (net (code "60") (name "/PA14") (class "Default")
      (node (ref "L") (pin "27") (pinfunction "27_27") (pintype "passive"))
    )
    (net (code "61") (name "/PA15") (class "Default")
      (node (ref "L") (pin "26") (pinfunction "26_26") (pintype "passive"))
    )
    (net (code "62") (name "/PB0") (class "Default")
      (node (ref "R") (pin "33") (pinfunction "33_33") (pintype "passive"))
    )
    (net (code "63") (name "/PB1") (class "Default")
      (node (ref "R") (pin "36") (pinfunction "36_36") (pintype "passive"))
    )
    (net (code "64") (name "/PB2") (class "Default")
      (node (ref "R") (pin "35") (pinfunction "35_35") (pintype "passive"))
    )
    (net (code "65") (name "/PB3") (class "Default")
      (node (ref "L") (pin "7") (pinfunction "7_7") (pintype "passive"))
    )
    (net (code "66") (name "/PB4") (class "Default")
      (node (ref "L") (pin "6") (pinfunction "6_6") (pintype "passive"))
    )
    (net (code "67") (name "/PB5") (class "Default")
      (node (ref "L") (pin "5") (pinfunction "5_5") (pintype "passive"))
      (node (ref "R147") (pin "1") (pinfunction "1_1") (pintype "passive"))
    )
    (net (code "68") (name "/PB6") (class "Default")
      (node (ref "L") (pin "4") (pinfunction "4_4") (pintype "passive"))
    )
    (net (code "69") (name "/PB7") (class "Default")
      (node (ref "L") (pin "3") (pinfunction "3_3") (pintype "passive"))
      (node (ref "R146") (pin "1") (pinfunction "1_1") (pintype "passive"))
    )
    (net (code "70") (name "/PB8") (class "Default")
      (node (ref "L") (pin "2") (pinfunction "2_2") (pintype "passive"))
    )
    (net (code "71") (name "/PB9") (class "Default")
      (node (ref "L") (pin "1") (pinfunction "1_1") (pintype "passive"))
      (node (ref "R145") (pin "1") (pinfunction "1_1") (pintype "passive"))
    )
    (net (code "72") (name "/PB10") (class "Default")
      (node (ref "R") (pin "54") (pinfunction "54_54") (pintype "passive"))
    )
    (net (code "73") (name "/PB11") (class "Default")
      (node (ref "R") (pin "53") (pinfunction "53_53") (pintype "passive"))
    )
    (net (code "74") (name "/PB12") (class "Default")
      (node (ref "L") (pin "56") (pinfunction "56_56") (pintype "passive"))
    )
    (net (code "75") (name "/PB13") (class "Default")
      (node (ref "L") (pin "55") (pinfunction "55_55") (pintype "passive"))
    )
    (net (code "76") (name "/PB14") (class "Default")
      (node (ref "L") (pin "54") (pinfunction "54_54") (pintype "passive"))
    )
    (net (code "77") (name "/PB15") (class "Default")
      (node (ref "L") (pin "53") (pinfunction "53_53") (pintype "passive"))
    )
    (net (code "78") (name "/PC0") (class "Default")
      (node (ref "R") (pin "19") (pinfunction "19_19") (pintype "passive"))
    )
    (net (code "79") (name "/PC1") (class "Default")
      (node (ref "R") (pin "22") (pinfunction "22_22") (pintype "passive"))
    )
    (net (code "80") (name "/PC2") (class "Default")
      (node (ref "R") (pin "21") (pinfunction "21_21") (pintype "passive"))
    )
    (net (code "81") (name "/PC3") (class "Default")
      (node (ref "R") (pin "24") (pinfunction "24_24") (pintype "passive"))
    )
    (net (code "82") (name "/PC4") (class "Default")
      (node (ref "R") (pin "31") (pinfunction "31_31") (pintype "passive"))
    )
    (net (code "83") (name "/PC5") (class "Default")
      (node (ref "R") (pin "34") (pinfunction "34_34") (pintype "passive"))
    )
    (net (code "84") (name "/PC6") (class "Default")
      (node (ref "L") (pin "37") (pinfunction "37_37") (pintype "passive"))
    )
    (net (code "85") (name "/PC7") (class "Default")
      (node (ref "L") (pin "36") (pinfunction "36_36") (pintype "passive"))
    )
    (net (code "86") (name "/PC8") (class "Default")
      (node (ref "L") (pin "35") (pinfunction "35_35") (pintype "passive"))
    )
    (net (code "87") (name "/PC9") (class "Default")
      (node (ref "L") (pin "34") (pinfunction "34_34") (pintype "passive"))
    )
    (net (code "88") (name "/PC10") (class "Default")
      (node (ref "L") (pin "25") (pinfunction "25_25") (pintype "passive"))
    )
    (net (code "89") (name "/PC11") (class "Default")
      (node (ref "L") (pin "24") (pinfunction "24_24") (pintype "passive"))
    )
    (net (code "90") (name "/PC12") (class "Default")
      (node (ref "L") (pin "23") (pinfunction "23_23") (pintype "passive"))
    )
    (net (code "91") (name "/PC13") (class "Default")
      (node (ref "R") (pin "7") (pinfunction "7_7") (pintype "passive"))
    )
    (net (code "92") (name "/PD0") (class "Default")
      (node (ref "L") (pin "22") (pinfunction "22_22") (pintype "passive"))
    )
    (net (code "93") (name "/PD1") (class "Default")
      (node (ref "L") (pin "21") (pinfunction "21_21") (pintype "passive"))
    )
    (net (code "94") (name "/PD2") (class "Default")
      (node (ref "L") (pin "20") (pinfunction "20_20") (pintype "passive"))
    )
    (net (code "95") (name "/PD3") (class "Default")
      (node (ref "L") (pin "19") (pinfunction "19_19") (pintype "passive"))
    )
    (net (code "96") (name "/PD4") (class "Default")
      (node (ref "L") (pin "18") (pinfunction "18_18") (pintype "passive"))
    )
    (net (code "97") (name "/PD5") (class "Default")
      (node (ref "L") (pin "17") (pinfunction "17_17") (pintype "passive"))
    )
    (net (code "98") (name "/PD6") (class "Default")
      (node (ref "L") (pin "16") (pinfunction "16_16") (pintype "passive"))
      (node (ref "R149") (pin "1") (pinfunction "1_1") (pintype "passive"))
    )
    (net (code "99") (name "/PD7") (class "Default")
      (node (ref "L") (pin "15") (pinfunction "15_15") (pintype "passive"))
      (node (ref "R148") (pin "1") (pinfunction "1_1") (pintype "passive"))
    )
    (net (code "100") (name "/PD8") (class "Default")
      (node (ref "L") (pin "52") (pinfunction "52_52") (pintype "passive"))
    )
    (net (code "101") (name "/PD9") (class "Default")
      (node (ref "L") (pin "51") (pinfunction "51_51") (pintype "passive"))
    )
    (net (code "102") (name "/PD10") (class "Default")
      (node (ref "L") (pin "50") (pinfunction "50_50") (pintype "passive"))
    )
    (net (code "103") (name "/PD11") (class "Default")
      (node (ref "L") (pin "49") (pinfunction "49_49") (pintype "passive"))
    )
    (net (code "104") (name "/PD12") (class "Default")
      (node (ref "L") (pin "48") (pinfunction "48_48") (pintype "passive"))
    )
    (net (code "105") (name "/PD13") (class "Default")
      (node (ref "L") (pin "47") (pinfunction "47_47") (pintype "passive"))
    )
    (net (code "106") (name "/PD14") (class "Default")
      (node (ref "L") (pin "46") (pinfunction "46_46") (pintype "passive"))
    )
    (net (code "107") (name "/PD15") (class "Default")
      (node (ref "L") (pin "45") (pinfunction "45_45") (pintype "passive"))
    )
    (net (code "108") (name "/PE0") (class "Default")
      (node (ref "C60") (pin "2") (pinfunction "2_2") (pintype "passive"))
      (node (ref "R") (pin "2") (pinfunction "2_2") (pintype "passive"))
      (node (ref "play") (pin "2") (pinfunction "2_2") (pintype "passive"))
    )
    (net (code "109") (name "/PE1") (class "Default")
      (node (ref "C61") (pin "2") (pinfunction "2_2") (pintype "passive"))
      (node (ref "R") (pin "1") (pinfunction "1_1") (pintype "passive"))
      (node (ref "mode") (pin "2") (pinfunction "2_2") (pintype "passive"))
    )
    (net (code "110") (name "/PE2") (class "Default")
      (node (ref "R") (pin "4") (pinfunction "4_4") (pintype "passive"))
    )
    (net (code "111") (name "/PE3") (class "Default")
      (node (ref "R") (pin "3") (pinfunction "3_3") (pintype "passive"))
    )
    (net (code "112") (name "/PE4") (class "Default")
      (node (ref "R") (pin "6") (pinfunction "6_6") (pintype "passive"))
    )
    (net (code "113") (name "/PE5") (class "Default")
      (node (ref "R") (pin "5") (pinfunction "5_5") (pintype "passive"))
    )
    (net (code "114") (name "/PE6") (class "Default")
      (node (ref "R") (pin "8") (pinfunction "8_8") (pintype "passive"))
    )
    (net (code "115") (name "/PE7") (class "Default")
      (node (ref "R") (pin "43") (pinfunction "43_43") (pintype "passive"))
    )
    (net (code "116") (name "/PE8") (class "Default")
      (node (ref "R") (pin "46") (pinfunction "46_46") (pintype "passive"))
    )
    (net (code "117") (name "/PE9") (class "Default")
      (node (ref "R") (pin "45") (pinfunction "45_45") (pintype "passive"))
    )
    (net (code "118") (name "/PE10") (class "Default")
      (node (ref "R") (pin "48") (pinfunction "48_48") (pintype "passive"))
    )
    (net (code "119") (name "/PE11") (class "Default")
      (node (ref "R") (pin "47") (pinfunction "47_47") (pintype "passive"))
    )
    (net (code "120") (name "/PE12") (class "Default")
      (node (ref "R") (pin "50") (pinfunction "50_50") (pintype "passive"))
      (node (ref "R144") (pin "1") (pinfunction "1_1") (pintype "passive"))
    )
    (net (code "121") (name "/PE13") (class "Default")
      (node (ref "R") (pin "49") (pinfunction "49_49") (pintype "passive"))
      (node (ref "R150") (pin "1") (pinfunction "1_1") (pintype "passive"))
    )
    (net (code "122") (name "/PE14") (class "Default")
      (node (ref "R") (pin "52") (pinfunction "52_52") (pintype "passive"))
      (node (ref "R143") (pin "1") (pinfunction "1_1") (pintype "passive"))
    )
    (net (code "123") (name "/PE15") (class "Default")
      (node (ref "R") (pin "51") (pinfunction "51_51") (pintype "passive"))
      (node (ref "R151") (pin "1") (pinfunction "1_1") (pintype "passive"))
    )
    (net (code "124") (name "/PF0") (class "Default")
      (node (ref "R") (pin "10") (pinfunction "10_10") (pintype "passive"))
    )
    (net (code "125") (name "/PF1") (class "Default")
      (node (ref "R") (pin "9") (pinfunction "9_9") (pintype "passive"))
    )
    (net (code "126") (name "/PF2") (class "Default")
      (node (ref "R") (pin "12") (pinfunction "12_12") (pintype "passive"))
    )
    (net (code "127") (name "/PF3") (class "Default")
      (node (ref "R") (pin "11") (pinfunction "11_11") (pintype "passive"))
    )
    (net (code "128") (name "/PF4") (class "Default")
      (node (ref "R") (pin "14") (pinfunction "14_14") (pintype "passive"))
    )
    (net (code "129") (name "/PF5") (class "Default")
      (node (ref "R") (pin "13") (pinfunction "13_13") (pintype "passive"))
    )
    (net (code "130") (name "/PF6") (class "Default")
      (node (ref "R") (pin "16") (pinfunction "16_16") (pintype "passive"))
    )
    (net (code "131") (name "/PF7") (class "Default")
      (node (ref "R") (pin "15") (pinfunction "15_15") (pintype "passive"))
    )
    (net (code "132") (name "/PF8") (class "Default")
      (node (ref "R") (pin "18") (pinfunction "18_18") (pintype "passive"))
    )
    (net (code "133") (name "/PF9") (class "Default")
      (node (ref "R") (pin "17") (pinfunction "17_17") (pintype "passive"))
    )
    (net (code "134") (name "/PF10") (class "Default")
      (node (ref "R") (pin "20") (pinfunction "20_20") (pintype "passive"))
    )
    (net (code "135") (name "/PF11") (class "Default")
      (node (ref "R") (pin "38") (pinfunction "38_38") (pintype "passive"))
    )
    (net (code "136") (name "/PF12") (class "Default")
      (node (ref "R") (pin "37") (pinfunction "37_37") (pintype "passive"))
    )
    (net (code "137") (name "/PF13") (class "Default")
      (node (ref "R") (pin "40") (pinfunction "40_40") (pintype "passive"))
    )
    (net (code "138") (name "/PF14") (class "Default")
      (node (ref "R") (pin "39") (pinfunction "39_39") (pintype "passive"))
    )
    (net (code "139") (name "/PF15") (class "Default")
      (node (ref "R") (pin "42") (pinfunction "42_42") (pintype "passive"))
    )
    (net (code "140") (name "/PG0") (class "Default")
      (node (ref "R") (pin "41") (pinfunction "41_41") (pintype "passive"))
    )
    (net (code "141") (name "/PG1") (class "Default")
      (node (ref "R") (pin "44") (pinfunction "44_44") (pintype "passive"))
    )
    (net (code "142") (name "/PG2") (class "Default")
      (node (ref "L") (pin "44") (pinfunction "44_44") (pintype "passive"))
    )
    (net (code "143") (name "/PG3") (class "Default")
      (node (ref "L") (pin "43") (pinfunction "43_43") (pintype "passive"))
    )
    (net (code "144") (name "/PG4") (class "Default")
      (node (ref "L") (pin "42") (pinfunction "42_42") (pintype "passive"))
    )
    (net (code "145") (name "/PG5") (class "Default")
      (node (ref "L") (pin "41") (pinfunction "41_41") (pintype "passive"))
    )
    (net (code "146") (name "/PG6") (class "Default")
      (node (ref "L") (pin "40") (pinfunction "40_40") (pintype "passive"))
    )
    (net (code "147") (name "/PG7") (class "Default")
      (node (ref "L") (pin "39") (pinfunction "39_39") (pintype "passive"))
    )
    (net (code "148") (name "/PG8") (class "Default")
      (node (ref "L") (pin "38") (pinfunction "38_38") (pintype "passive"))
    )
    (net (code "149") (name "/PG9") (class "Default")
      (node (ref "L") (pin "14") (pinfunction "14_14") (pintype "passive"))
    )
    (net (code "150") (name "/PG10") (class "Default")
      (node (ref "L") (pin "13") (pinfunction "13_13") (pintype "passive"))
    )
    (net (code "151") (name "/PG11") (class "Default")
      (node (ref "L") (pin "12") (pinfunction "12_12") (pintype "passive"))
    )
    (net (code "152") (name "/PG12") (class "Default")
      (node (ref "L") (pin "11") (pinfunction "11_11") (pintype "passive"))
    )
    (net (code "153") (name "/PG13") (class "Default")
      (node (ref "L") (pin "10") (pinfunction "10_10") (pintype "passive"))
    )
    (net (code "154") (name "/PG14") (class "Default")
      (node (ref "L") (pin "9") (pinfunction "9_9") (pintype "passive"))
    )
    (net (code "155") (name "/PG15") (class "Default")
      (node (ref "L") (pin "8") (pinfunction "8_8") (pintype "passive"))
    )
    (net (code "156") (name "/RCK") (class "Default")
      (node (ref "AR0") (pin "12") (pinfunction "RCK_12") (pintype "passive"))
      (node (ref "AR1") (pin "12") (pinfunction "RCK_12") (pintype "passive"))
      (node (ref "AR2") (pin "12") (pinfunction "RCK_12") (pintype "passive"))
      (node (ref "AR3") (pin "12") (pinfunction "RCK_12") (pintype "passive"))
      (node (ref "CL0") (pin "12") (pinfunction "RCK_12") (pintype "passive"))
      (node (ref "CL1") (pin "12") (pinfunction "RCK_12") (pintype "passive"))
      (node (ref "R147") (pin "2") (pinfunction "2_2") (pintype "passive"))
    )
    (net (code "157") (name "/ROUTN") (class "Default")
      (node (ref "C28") (pin "2") (pinfunction "2_2") (pintype "passive"))
      (node (ref "JP2") (pin "2") (pinfunction "2_2") (pintype "passive"))
      (node (ref "U1") (pin "37") (pinfunction "ROUTN_37") (pintype "output"))
      (node (ref "U1") (pin "38") (pinfunction "ROUTN_38") (pintype "output"))
    )
    (net (code "158") (name "/ROUTP") (class "Default")
      (node (ref "C25") (pin "2") (pinfunction "2_2") (pintype "passive"))
      (node (ref "JP2") (pin "1") (pinfunction "1_1") (pintype "passive"))
      (node (ref "U1") (pin "33") (pinfunction "ROUTP_33") (pintype "output"))
      (node (ref "U1") (pin "34") (pinfunction "ROUTP_34") (pintype "output"))
    )
    (net (code "159") (name "/SCK") (class "Default")
      (node (ref "AR0") (pin "11") (pinfunction "SCK_11") (pintype "passive"))
      (node (ref "AR1") (pin "11") (pinfunction "SCK_11") (pintype "passive"))
      (node (ref "AR2") (pin "11") (pinfunction "SCK_11") (pintype "passive"))
      (node (ref "AR3") (pin "11") (pinfunction "SCK_11") (pintype "passive"))
      (node (ref "CL0") (pin "11") (pinfunction "SCK_11") (pintype "passive"))
      (node (ref "CL1") (pin "11") (pinfunction "SCK_11") (pintype "passive"))
      (node (ref "R146") (pin "2") (pinfunction "2_2") (pintype "passive"))
    )
    (net (code "160") (name "/SDIL0") (class "Default")
      (node (ref "CL0") (pin "14") (pinfunction "SIN_14") (pintype "passive"))
      (node (ref "R144") (pin "2") (pinfunction "2_2") (pintype "passive"))
    )
    (net (code "161") (name "/SDIL1") (class "Default")
      (node (ref "CL1") (pin "14") (pinfunction "SIN_14") (pintype "passive"))
      (node (ref "R143") (pin "2") (pinfunction "2_2") (pintype "passive"))
    )
    (net (code "162") (name "/SDIR0") (class "Default")
      (node (ref "AR0") (pin "14") (pinfunction "SIN_14") (pintype "passive"))
      (node (ref "R148") (pin "2") (pinfunction "2_2") (pintype "passive"))
    )
    (net (code "163") (name "/SDIR1") (class "Default")
      (node (ref "AR1") (pin "14") (pinfunction "SIN_14") (pintype "passive"))
      (node (ref "R149") (pin "2") (pinfunction "2_2") (pintype "passive"))
    )
    (net (code "164") (name "/SDIR2") (class "Default")
      (node (ref "AR2") (pin "14") (pinfunction "SIN_14") (pintype "passive"))
      (node (ref "R150") (pin "2") (pinfunction "2_2") (pintype "passive"))
    )
    (net (code "165") (name "/SDIR3") (class "Default")
      (node (ref "AR3") (pin "14") (pinfunction "SIN_14") (pintype "passive"))
      (node (ref "R151") (pin "2") (pinfunction "2_2") (pintype "passive"))
    )
    (net (code "166") (name "3V3") (class "Default")
      (node (ref "3.3V") (pin "2") (pinfunction "OUT_2") (pintype "passive"))
      (node (ref "AR0") (pin "16") (pinfunction "VCC_16") (pintype "passive"))
      (node (ref "AR1") (pin "16") (pinfunction "VCC_16") (pintype "passive"))
      (node (ref "AR2") (pin "16") (pinfunction "VCC_16") (pintype "passive"))
      (node (ref "AR3") (pin "16") (pinfunction "VCC_16") (pintype "passive"))
      (node (ref "C10") (pin "1") (pinfunction "1_1") (pintype "passive"))
      (node (ref "C4") (pin "1") (pinfunction "1_1") (pintype "passive"))
      (node (ref "C46") (pin "2") (pinfunction "2_2") (pintype "passive"))
      (node (ref "C47") (pin "1") (pinfunction "1_1") (pintype "passive"))
      (node (ref "C5") (pin "1") (pinfunction "1_1") (pintype "passive"))
      (node (ref "C6") (pin "1") (pinfunction "1_1") (pintype "passive"))
      (node (ref "C7") (pin "1") (pinfunction "1_1") (pintype "passive"))
      (node (ref "C9") (pin "1") (pinfunction "1_1") (pintype "passive"))
      (node (ref "CL0") (pin "16") (pinfunction "VCC_16") (pintype "passive"))
      (node (ref "CL1") (pin "16") (pinfunction "VCC_16") (pintype "passive"))
    )
    (net (code "167") (name "5V") (class "Default")
      (node (ref "3.3V") (pin "3") (pinfunction "VIN_3") (pintype "passive"))
      (node (ref "5V") (pin "2") (pinfunction "OUT_2") (pintype "passive"))
      (node (ref "C42") (pin "2") (pinfunction "2_2") (pintype "passive"))
      (node (ref "C43") (pin "1") (pinfunction "1_1") (pintype "passive"))
      (node (ref "C59") (pin "2") (pinfunction "2_2") (pintype "passive"))
      (node (ref "USBA") (pin "1") (pinfunction "VCC_1") (pintype "passive"))
    )
    (net (code "168") (name "7V") (class "Default")
      (node (ref "5V") (pin "3") (pinfunction "VIN_3") (pintype "passive"))
      (node (ref "C40") (pin "2") (pinfunction "2_2") (pintype "passive"))
      (node (ref "C41") (pin "2") (pinfunction "2_2") (pintype "passive"))
      (node (ref "E1") (pin "1") (pinfunction "A_1") (pintype "passive"))
      (node (ref "L1") (pin "2") (pinfunction "2_2") (pintype "passive"))
      (node (ref "R82") (pin "2") (pinfunction "2_2") (pintype "passive"))
    )
    (net (code "169") (name "12V") (class "Default")
      (node (ref "C15") (pin "1") (pinfunction "1_1") (pintype "passive"))
      (node (ref "C23") (pin "1") (pinfunction "1_1") (pintype "passive"))
      (node (ref "C51") (pin "2") (pinfunction "2_2") (pintype "passive"))
      (node (ref "C52") (pin "2") (pinfunction "2_2") (pintype "passive"))
      (node (ref "FB1") (pin "2") (pinfunction "2_2") (pintype "passive"))
      (node (ref "LED1") (pin "1") (pinfunction "A_1") (pintype "passive"))
      (node (ref "U1") (pin "26") (pinfunction "AVCC_26") (pintype "passive"))
      (node (ref "U5") (pin "7") (pinfunction "VIN_7") (pintype "passive"))
    )
    (net (code "170") (name "GND") (class "Default")
      (node (ref "3.3V") (pin "1") (pinfunction "GND_1") (pintype "passive"))
      (node (ref "5V") (pin "1") (pinfunction "GND_1") (pintype "passive"))
      (node (ref "AR0") (pin "13") (pinfunction "~{OE}_13") (pintype "passive"))
      (node (ref "AR0") (pin "8") (pinfunction "GND_8") (pintype "passive"))
      (node (ref "AR1") (pin "13") (pinfunction "~{OE}_13") (pintype "passive"))
      (node (ref "AR1") (pin "8") (pinfunction "GND_8") (pintype "passive"))
      (node (ref "AR2") (pin "13") (pinfunction "~{OE}_13") (pintype "passive"))
      (node (ref "AR2") (pin "8") (pinfunction "GND_8") (pintype "passive"))
      (node (ref "AR3") (pin "13") (pinfunction "~{OE}_13") (pintype "passive"))
      (node (ref "AR3") (pin "8") (pinfunction "GND_8") (pintype "passive"))
      (node (ref "C10") (pin "2") (pinfunction "2_2") (pintype "passive"))
      (node (ref "C15") (pin "2") (pinfunction "2_2") (pintype "passive"))
      (node (ref "C16") (pin "1") (pinfunction "1_1") (pintype "passive"))
      (node (ref "C17") (pin "1") (pinfunction "1_1") (pintype "passive"))
      (node (ref "C19") (pin "1") (pinfunction "1_1") (pintype "passive"))
      (node (ref "C21") (pin "1") (pinfunction "1_1") (pintype "passive"))
      (node (ref "C23") (pin "2") (pinfunction "2_2") (pintype "passive"))
      (node (ref "C24") (pin "2") (pinfunction "2_2") (pintype "passive"))
      (node (ref "C29") (pin "1") (pinfunction "1_1") (pintype "passive"))
      (node (ref "C30") (pin "1") (pinfunction "1_1") (pintype "passive"))
      (node (ref "C31") (pin "1") (pinfunction "1_1") (pintype "passive"))
      (node (ref "C32") (pin "1") (pinfunction "1_1") (pintype "passive"))
      (node (ref "C33") (pin "1") (pinfunction "1_1") (pintype "passive"))
      (node (ref "C34") (pin "1") (pinfunction "1_1") (pintype "passive"))
      (node (ref "C4") (pin "2") (pinfunction "2_2") (pintype "passive"))
      (node (ref "C40") (pin "1") (pinfunction "1_1") (pintype "passive"))
      (node (ref "C41") (pin "1") (pinfunction "1_1") (pintype "passive"))
      (node (ref "C42") (pin "1") (pinfunction "1_1") (pintype "passive"))
      (node (ref "C43") (pin "2") (pinfunction "2_2") (pintype "passive"))
      (node (ref "C46") (pin "1") (pinfunction "1_1") (pintype "passive"))
      (node (ref "C47") (pin "2") (pinfunction "2_2") (pintype "passive"))
      (node (ref "C5") (pin "2") (pinfunction "2_2") (pintype "passive"))
      (node (ref "C51") (pin "1") (pinfunction "1_1") (pintype "passive"))
      (node (ref "C52") (pin "1") (pinfunction "1_1") (pintype "passive"))
      (node (ref "C59") (pin "1") (pinfunction "1_1") (pintype "passive"))
      (node (ref "C6") (pin "2") (pinfunction "2_2") (pintype "passive"))
      (node (ref "C60") (pin "1") (pinfunction "1_1") (pintype "passive"))
      (node (ref "C61") (pin "1") (pinfunction "1_1") (pintype "passive"))
      (node (ref "C7") (pin "2") (pinfunction "2_2") (pintype "passive"))
      (node (ref "C9") (pin "2") (pinfunction "2_2") (pintype "passive"))
      (node (ref "CL0") (pin "13") (pinfunction "~{OE}_13") (pintype "passive"))
      (node (ref "CL0") (pin "8") (pinfunction "GND_8") (pintype "passive"))
      (node (ref "CL1") (pin "13") (pinfunction "~{OE}_13") (pintype "passive"))
      (node (ref "CL1") (pin "8") (pinfunction "GND_8") (pintype "passive"))
      (node (ref "D1") (pin "1") (pinfunction "A_1") (pintype "passive"))
      (node (ref "E1") (pin "2") (pinfunction "K_2") (pintype "passive"))
      (node (ref "FB2") (pin "2") (pinfunction "2_2") (pintype "passive"))
      (node (ref "L") (pin "58") (pinfunction "58_58") (pintype "passive"))
      (node (ref "L") (pin "60") (pinfunction "60_60") (pintype "passive"))
      (node (ref "R") (pin "55") (pinfunction "55_55") (pintype "passive"))
      (node (ref "R") (pin "56") (pinfunction "56_56") (pintype "passive"))
      (node (ref "R72") (pin "1") (pinfunction "1_1") (pintype "passive"))
      (node (ref "R83") (pin "1") (pinfunction "1_1") (pintype "passive"))
      (node (ref "R84") (pin "1") (pinfunction "1_1") (pintype "passive"))
      (node (ref "RP1") (pin "3") (pinfunction "3_3") (pintype "passive"))
      (node (ref "U1") (pin "11") (pinfunction "PGNDL_11") (pintype "passive"))
      (node (ref "U1") (pin "20") (pinfunction "PGNDL_20") (pintype "passive"))
      (node (ref "U1") (pin "24") (pinfunction "AGND_24") (pintype "passive"))
      (node (ref "U1") (pin "25") (pinfunction "MUTE_25") (pintype "passive"))
      (node (ref "U1") (pin "28") (pinfunction "AGND_28") (pintype "passive"))
      (node (ref "U1") (pin "31") (pinfunction "PGNDR_31") (pintype "passive"))
      (node (ref "U1") (pin "40") (pinfunction "PGNDR_40") (pintype "passive"))
      (node (ref "U1") (pin "41") (pinfunction "41_41") (pintype "passive"))
      (node (ref "U1") (pin "6") (pinfunction "REFGND_6") (pintype "passive"))
      (node (ref "U1") (pin "7") (pinfunction "AGND1_7") (pintype "passive"))
      (node (ref "U1") (pin "8") (pinfunction "FADE_8") (pintype "passive"))
      (node (ref "U5") (pin "6") (pinfunction "GND_6") (pintype "passive"))
      (node (ref "U5") (pin "9") (pinfunction "PAD_9") (pintype "passive"))
      (node (ref "USBA") (pin "4") (pinfunction "GND_4") (pintype "passive"))
      (node (ref "mode") (pin "1") (pinfunction "1_1") (pintype "passive"))
      (node (ref "play") (pin "1") (pinfunction "1_1") (pintype "passive"))
    )
    (net (code "171") (name "GNDin") (class "Default")
      (node (ref "C36") (pin "1") (pinfunction "1_1") (pintype "passive"))
      (node (ref "C37") (pin "1") (pinfunction "1_1") (pintype "passive"))
      (node (ref "CON1") (pin "2") (pintype "power_in"))
      (node (ref "CON1") (pin "3") (pintype "power_in"))
      (node (ref "FB2") (pin "1") (pinfunction "1_1") (pintype "passive"))
    )
    (net (code "172") (name "Net-(AR0-Q0)") (class "Default")
      (node (ref "AR0") (pin "15") (pinfunction "Q0_15") (pintype "passive"))
      (node (ref "R0") (pin "1") (pinfunction "1_1") (pintype "passive"))
    )
    (net (code "173") (name "Net-(AR0-Q1)") (class "Default")
      (node (ref "AR0") (pin "1") (pinfunction "Q1_1") (pintype "passive"))
      (node (ref "R1") (pin "2") (pinfunction "2_2") (pintype "passive"))
    )
    (net (code "174") (name "Net-(AR0-Q2)") (class "Default")
      (node (ref "AR0") (pin "2") (pinfunction "Q2_2") (pintype "passive"))
      (node (ref "R2") (pin "2") (pinfunction "2_2") (pintype "passive"))
    )
    (net (code "175") (name "Net-(AR0-Q3)") (class "Default")
      (node (ref "AR0") (pin "3") (pinfunction "Q3_3") (pintype "passive"))
      (node (ref "R3") (pin "2") (pinfunction "2_2") (pintype "passive"))
    )
    (net (code "176") (name "Net-(AR0-Q4)") (class "Default")
      (node (ref "AR0") (pin "4") (pinfunction "Q4_4") (pintype "passive"))
      (node (ref "R4") (pin "2") (pinfunction "2_2") (pintype "passive"))
    )
    (net (code "177") (name "Net-(AR0-Q5)") (class "Default")
      (node (ref "AR0") (pin "5") (pinfunction "Q5_5") (pintype "passive"))
      (node (ref "R5") (pin "2") (pinfunction "2_2") (pintype "passive"))
    )
    (net (code "178") (name "Net-(AR0-Q6)") (class "Default")
      (node (ref "AR0") (pin "6") (pinfunction "Q6_6") (pintype "passive"))
      (node (ref "R6") (pin "2") (pinfunction "2_2") (pintype "passive"))
    )
    (net (code "179") (name "Net-(AR0-Q7)") (class "Default")
      (node (ref "AR0") (pin "7") (pinfunction "Q7_7") (pintype "passive"))
      (node (ref "R7") (pin "2") (pinfunction "2_2") (pintype "passive"))
    )
    (net (code "180") (name "Net-(AR1-Q0)") (class "Default")
      (node (ref "AR1") (pin "15") (pinfunction "Q0_15") (pintype "passive"))
      (node (ref "R8") (pin "1") (pinfunction "1_1") (pintype "passive"))
    )
    (net (code "181") (name "Net-(AR1-Q1)") (class "Default")
      (node (ref "AR1") (pin "1") (pinfunction "Q1_1") (pintype "passive"))
      (node (ref "R9") (pin "2") (pinfunction "2_2") (pintype "passive"))
    )
    (net (code "182") (name "Net-(AR1-Q2)") (class "Default")
      (node (ref "AR1") (pin "2") (pinfunction "Q2_2") (pintype "passive"))
      (node (ref "R10") (pin "2") (pinfunction "2_2") (pintype "passive"))
    )
    (net (code "183") (name "Net-(AR1-Q3)") (class "Default")
      (node (ref "AR1") (pin "3") (pinfunction "Q3_3") (pintype "passive"))
      (node (ref "R11") (pin "2") (pinfunction "2_2") (pintype "passive"))
    )
    (net (code "184") (name "Net-(AR1-Q4)") (class "Default")
      (node (ref "AR1") (pin "4") (pinfunction "Q4_4") (pintype "passive"))
      (node (ref "R12") (pin "2") (pinfunction "2_2") (pintype "passive"))
    )
    (net (code "185") (name "Net-(AR1-Q5)") (class "Default")
      (node (ref "AR1") (pin "5") (pinfunction "Q5_5") (pintype "passive"))
      (node (ref "R13") (pin "2") (pinfunction "2_2") (pintype "passive"))
    )
    (net (code "186") (name "Net-(AR1-Q6)") (class "Default")
      (node (ref "AR1") (pin "6") (pinfunction "Q6_6") (pintype "passive"))
      (node (ref "R14") (pin "2") (pinfunction "2_2") (pintype "passive"))
    )
    (net (code "187") (name "Net-(AR1-Q7)") (class "Default")
      (node (ref "AR1") (pin "7") (pinfunction "Q7_7") (pintype "passive"))
      (node (ref "R15") (pin "2") (pinfunction "2_2") (pintype "passive"))
    )
    (net (code "188") (name "Net-(AR2-Q0)") (class "Default")
      (node (ref "AR2") (pin "15") (pinfunction "Q0_15") (pintype "passive"))
      (node (ref "R16") (pin "1") (pinfunction "1_1") (pintype "passive"))
    )
    (net (code "189") (name "Net-(AR2-Q1)") (class "Default")
      (node (ref "AR2") (pin "1") (pinfunction "Q1_1") (pintype "passive"))
      (node (ref "R17") (pin "2") (pinfunction "2_2") (pintype "passive"))
    )
    (net (code "190") (name "Net-(AR2-Q2)") (class "Default")
      (node (ref "AR2") (pin "2") (pinfunction "Q2_2") (pintype "passive"))
      (node (ref "R18") (pin "2") (pinfunction "2_2") (pintype "passive"))
    )
    (net (code "191") (name "Net-(AR2-Q3)") (class "Default")
      (node (ref "AR2") (pin "3") (pinfunction "Q3_3") (pintype "passive"))
      (node (ref "R19") (pin "2") (pinfunction "2_2") (pintype "passive"))
    )
    (net (code "192") (name "Net-(AR2-Q4)") (class "Default")
      (node (ref "AR2") (pin "4") (pinfunction "Q4_4") (pintype "passive"))
      (node (ref "R20") (pin "2") (pinfunction "2_2") (pintype "passive"))
    )
    (net (code "193") (name "Net-(AR2-Q5)") (class "Default")
      (node (ref "AR2") (pin "5") (pinfunction "Q5_5") (pintype "passive"))
      (node (ref "R21") (pin "2") (pinfunction "2_2") (pintype "passive"))
    )
    (net (code "194") (name "Net-(AR2-Q6)") (class "Default")
      (node (ref "AR2") (pin "6") (pinfunction "Q6_6") (pintype "passive"))
      (node (ref "R22") (pin "2") (pinfunction "2_2") (pintype "passive"))
    )
    (net (code "195") (name "Net-(AR2-Q7)") (class "Default")
      (node (ref "AR2") (pin "7") (pinfunction "Q7_7") (pintype "passive"))
      (node (ref "R23") (pin "2") (pinfunction "2_2") (pintype "passive"))
    )
    (net (code "196") (name "Net-(AR3-Q0)") (class "Default")
      (node (ref "AR3") (pin "15") (pinfunction "Q0_15") (pintype "passive"))
      (node (ref "R24") (pin "1") (pinfunction "1_1") (pintype "passive"))
    )
    (net (code "197") (name "Net-(AR3-Q1)") (class "Default")
      (node (ref "AR3") (pin "1") (pinfunction "Q1_1") (pintype "passive"))
      (node (ref "R25") (pin "2") (pinfunction "2_2") (pintype "passive"))
    )
    (net (code "198") (name "Net-(AR3-Q2)") (class "Default")
      (node (ref "AR3") (pin "2") (pinfunction "Q2_2") (pintype "passive"))
      (node (ref "R26") (pin "2") (pinfunction "2_2") (pintype "passive"))
    )
    (net (code "199") (name "Net-(AR3-Q3)") (class "Default")
      (node (ref "AR3") (pin "3") (pinfunction "Q3_3") (pintype "passive"))
      (node (ref "R27") (pin "2") (pinfunction "2_2") (pintype "passive"))
    )
    (net (code "200") (name "Net-(AR3-Q4)") (class "Default")
      (node (ref "AR3") (pin "4") (pinfunction "Q4_4") (pintype "passive"))
      (node (ref "R28") (pin "2") (pinfunction "2_2") (pintype "passive"))
    )
    (net (code "201") (name "Net-(AR3-Q5)") (class "Default")
      (node (ref "AR3") (pin "5") (pinfunction "Q5_5") (pintype "passive"))
      (node (ref "R29") (pin "2") (pinfunction "2_2") (pintype "passive"))
    )
    (net (code "202") (name "Net-(C31-Pad2)") (class "Default")
      (node (ref "C31") (pin "2") (pinfunction "2_2") (pintype "passive"))
      (node (ref "U1") (pin "39") (pinfunction "PVCCR_39") (pintype "passive"))
    )
    (net (code "203") (name "Net-(C32-Pad2)") (class "Default")
      (node (ref "C32") (pin "2") (pinfunction "2_2") (pintype "passive"))
      (node (ref "U1") (pin "32") (pinfunction "PVCCR_32") (pintype "passive"))
    )
    (net (code "204") (name "Net-(C33-Pad2)") (class "Default")
      (node (ref "C33") (pin "2") (pinfunction "2_2") (pintype "passive"))
      (node (ref "U1") (pin "19") (pinfunction "PVCCL_19") (pintype "passive"))
    )
    (net (code "205") (name "Net-(C34-Pad2)") (class "Default")
      (node (ref "C34") (pin "2") (pinfunction "2_2") (pintype "passive"))
      (node (ref "U1") (pin "12") (pinfunction "PVCCL_12") (pintype "passive"))
    )
    (net (code "206") (name "Net-(CL0-Q0)") (class "Default")
      (node (ref "CL0") (pin "15") (pinfunction "Q0_15") (pintype "passive"))
      (node (ref "R40") (pin "1") (pinfunction "1_1") (pintype "passive"))
    )
    (net (code "207") (name "Net-(CL0-Q1)") (class "Default")
      (node (ref "CL0") (pin "1") (pinfunction "Q1_1") (pintype "passive"))
      (node (ref "R41") (pin "2") (pinfunction "2_2") (pintype "passive"))
    )
    (net (code "208") (name "Net-(CL0-Q2)") (class "Default")
      (node (ref "CL0") (pin "2") (pinfunction "Q2_2") (pintype "passive"))
      (node (ref "R42") (pin "2") (pinfunction "2_2") (pintype "passive"))
    )
    (net (code "209") (name "Net-(CL0-Q3)") (class "Default")
      (node (ref "CL0") (pin "3") (pinfunction "Q3_3") (pintype "passive"))
      (node (ref "R43") (pin "2") (pinfunction "2_2") (pintype "passive"))
    )
    (net (code "210") (name "Net-(CL0-Q4)") (class "Default")
      (node (ref "CL0") (pin "4") (pinfunction "Q4_4") (pintype "passive"))
      (node (ref "R44") (pin "2") (pinfunction "2_2") (pintype "passive"))
    )
    (net (code "211") (name "Net-(CL0-Q5)") (class "Default")
      (node (ref "CL0") (pin "5") (pinfunction "Q5_5") (pintype "passive"))
      (node (ref "R45") (pin "2") (pinfunction "2_2") (pintype "passive"))
    )
    (net (code "212") (name "Net-(CL0-Q6)") (class "Default")
      (node (ref "CL0") (pin "6") (pinfunction "Q6_6") (pintype "passive"))
      (node (ref "R46") (pin "2") (pinfunction "2_2") (pintype "passive"))
    )
    (net (code "213") (name "Net-(CL0-Q7)") (class "Default")
      (node (ref "CL0") (pin "7") (pinfunction "Q7_7") (pintype "passive"))
      (node (ref "R47") (pin "2") (pinfunction "2_2") (pintype "passive"))
    )
    (net (code "214") (name "Net-(CL1-Q0)") (class "Default")
      (node (ref "CL1") (pin "15") (pinfunction "Q0_15") (pintype "passive"))
      (node (ref "R48") (pin "1") (pinfunction "1_1") (pintype "passive"))
    )
    (net (code "215") (name "Net-(CL1-Q1)") (class "Default")
      (node (ref "CL1") (pin "1") (pinfunction "Q1_1") (pintype "passive"))
      (node (ref "R49") (pin "2") (pinfunction "2_2") (pintype "passive"))
    )
    (net (code "216") (name "Net-(D1-K)") (class "Default")
      (node (ref "C53") (pin "1") (pinfunction "1_1") (pintype "passive"))
      (node (ref "D1") (pin "2") (pinfunction "K_2") (pintype "passive"))
      (node (ref "L1") (pin "1") (pinfunction "1_1") (pintype "passive"))
      (node (ref "U5") (pin "8") (pinfunction "SW_8") (pintype "passive"))
    )
    (net (code "217") (name "Net-(LED1-K)") (class "Default")
      (node (ref "LED1") (pin "2") (pinfunction "K_2") (pintype "passive"))
      (node (ref "R84") (pin "2") (pinfunction "2_2") (pintype "passive"))
    )
    (net (code "218") (name "Net-(U1A-BRSN)") (class "Default")
      (node (ref "C28") (pin "1") (pinfunction "1_1") (pintype "passive"))
      (node (ref "U1") (pin "36") (pinfunction "BRSN_36") (pintype "passive"))
    )
    (net (code "219") (name "Net-(U1A-BSLN)") (class "Default")
      (node (ref "C27") (pin "1") (pinfunction "1_1") (pintype "passive"))
      (node (ref "U1") (pin "15") (pinfunction "BSLN_15") (pintype "passive"))
    )
    (net (code "220") (name "Net-(U1A-BSLP)") (class "Default")
      (node (ref "C26") (pin "1") (pinfunction "1_1") (pintype "passive"))
      (node (ref "U1") (pin "16") (pinfunction "BSLP_16") (pintype "passive"))
    )
    (net (code "221") (name "Net-(U1A-BSRP)") (class "Default")
      (node (ref "C25") (pin "1") (pinfunction "1_1") (pintype "passive"))
      (node (ref "U1") (pin "35") (pinfunction "BSRP_35") (pintype "passive"))
    )
    (net (code "222") (name "Net-(U1A-COSC)") (class "Default")
      (node (ref "C16") (pin "2") (pinfunction "2_2") (pintype "passive"))
      (node (ref "U1") (pin "22") (pinfunction "COSC_22") (pintype "passive"))
    )
    (net (code "223") (name "Net-(U1A-LINN)") (class "Default")
      (node (ref "C17") (pin "2") (pinfunction "2_2") (pintype "passive"))
      (node (ref "U1") (pin "10") (pinfunction "LINN_10") (pintype "passive"))
    )
    (net (code "224") (name "Net-(U1A-LINP)") (class "Default")
      (node (ref "C18") (pin "2") (pinfunction "2_2") (pintype "passive"))
      (node (ref "U1") (pin "9") (pinfunction "LINP_9") (pintype "passive"))
    )
    (net (code "225") (name "Net-(U1A-RINN)") (class "Default")
      (node (ref "C19") (pin "2") (pinfunction "2_2") (pintype "passive"))
      (node (ref "U1") (pin "1") (pinfunction "RINN_1") (pintype "passive"))
    )
    (net (code "226") (name "Net-(U1A-RINP)") (class "Default")
      (node (ref "C20") (pin "2") (pinfunction "2_2") (pintype "passive"))
      (node (ref "U1") (pin "2") (pinfunction "RINP_2") (pintype "passive"))
    )
    (net (code "227") (name "Net-(U1A-ROSC)") (class "Default")
      (node (ref "R72") (pin "2") (pinfunction "2_2") (pintype "passive"))
      (node (ref "U1") (pin "23") (pinfunction "ROSC_23") (pintype "passive"))
    )
    (net (code "228") (name "Net-(U1A-V2P5)") (class "Default")
      (node (ref "C21") (pin "2") (pinfunction "2_2") (pintype "passive"))
      (node (ref "U1") (pin "27") (pinfunction "V2P5_27") (pintype "passive"))
    )
    (net (code "229") (name "Net-(U1A-VCLAMPL)") (class "Default")
      (node (ref "C29") (pin "2") (pinfunction "2_2") (pintype "passive"))
      (node (ref "U1") (pin "21") (pinfunction "VCLAMPL_21") (pintype "passive"))
    )
    (net (code "230") (name "Net-(U1A-VCLAMPR)") (class "Default")
      (node (ref "C30") (pin "2") (pinfunction "2_2") (pintype "passive"))
      (node (ref "U1") (pin "30") (pinfunction "VCLAMPR_30") (pintype "passive"))
    )
    (net (code "231") (name "Net-(U1A-VOLUME)") (class "Default")
      (node (ref "RP1") (pin "2") (pinfunction "2_2") (pintype "passive"))
      (node (ref "U1") (pin "5") (pinfunction "VOLUME_5") (pintype "passive"))
    )
    (net (code "232") (name "Net-(U5-BT)") (class "Default")
      (node (ref "C53") (pin "2") (pinfunction "2_2") (pintype "passive"))
      (node (ref "U5") (pin "1") (pinfunction "BT_1") (pintype "passive"))
    )
    (net (code "233") (name "Net-(U5-FB)") (class "Default")
      (node (ref "R82") (pin "1") (pinfunction "1_1") (pintype "passive"))
      (node (ref "R83") (pin "2") (pinfunction "2_2") (pintype "passive"))
      (node (ref "U5") (pin "4") (pinfunction "FB_4") (pintype "passive"))
    )
    (net (code "234") (name "Vin") (class "Default")
      (node (ref "C36") (pin "2") (pinfunction "2_2") (pintype "passive"))
      (node (ref "C37") (pin "2") (pinfunction "2_2") (pintype "passive"))
      (node (ref "CON1") (pin "1") (pintype "power_in"))
      (node (ref "FB1") (pin "1") (pinfunction "1_1") (pintype "passive"))
    )
    (net (code "235") (name "unconnected-(AR0-SOUT-Pad9)") (class "Default")
      (node (ref "AR0") (pin "9") (pinfunction "SOUT_9") (pintype "passive"))
    )
    (net (code "236") (name "unconnected-(AR1-SOUT-Pad9)") (class "Default")
      (node (ref "AR1") (pin "9") (pinfunction "SOUT_9") (pintype "passive"))
    )
    (net (code "237") (name "unconnected-(AR2-SOUT-Pad9)") (class "Default")
      (node (ref "AR2") (pin "9") (pinfunction "SOUT_9") (pintype "passive"))
    )
    (net (code "238") (name "unconnected-(AR3-Q6-Pad6)") (class "Default")
      (node (ref "AR3") (pin "6") (pinfunction "Q6_6") (pintype "passive"))
    )
    (net (code "239") (name "unconnected-(AR3-Q7-Pad7)") (class "Default")
      (node (ref "AR3") (pin "7") (pinfunction "Q7_7") (pintype "passive"))
    )
    (net (code "240") (name "unconnected-(AR3-SOUT-Pad9)") (class "Default")
      (node (ref "AR3") (pin "9") (pinfunction "SOUT_9") (pintype "passive"))
    )
    (net (code "241") (name "unconnected-(CL0-SOUT-Pad9)") (class "Default")
      (node (ref "CL0") (pin "9") (pinfunction "SOUT_9") (pintype "passive"))
    )
    (net (code "242") (name "unconnected-(CL1-Q2-Pad2)") (class "Default")
      (node (ref "CL1") (pin "2") (pinfunction "Q2_2") (pintype "passive+no_connect"))
    )
    (net (code "243") (name "unconnected-(CL1-Q3-Pad3)") (class "Default")
      (node (ref "CL1") (pin "3") (pinfunction "Q3_3") (pintype "passive+no_connect"))
    )
    (net (code "244") (name "unconnected-(CL1-Q4-Pad4)") (class "Default")
      (node (ref "CL1") (pin "4") (pinfunction "Q4_4") (pintype "passive+no_connect"))
    )
    (net (code "245") (name "unconnected-(CL1-Q5-Pad5)") (class "Default")
      (node (ref "CL1") (pin "5") (pinfunction "Q5_5") (pintype "passive+no_connect"))
    )
    (net (code "246") (name "unconnected-(CL1-Q6-Pad6)") (class "Default")
      (node (ref "CL1") (pin "6") (pinfunction "Q6_6") (pintype "passive+no_connect"))
    )
    (net (code "247") (name "unconnected-(CL1-Q7-Pad7)") (class "Default")
      (node (ref "CL1") (pin "7") (pinfunction "Q7_7") (pintype "passive+no_connect"))
    )
    (net (code "248") (name "unconnected-(CL1-SOUT-Pad9)") (class "Default")
      (node (ref "CL1") (pin "9") (pinfunction "SOUT_9") (pintype "passive"))
    )
    (net (code "249") (name "unconnected-(L-Pad57)") (class "Default")
      (node (ref "L") (pin "57") (pinfunction "57_57") (pintype "passive"))
    )
    (net (code "250") (name "unconnected-(L-Pad59)") (class "Default")
      (node (ref "L") (pin "59") (pinfunction "59_59") (pintype "passive"))
    )
    (net (code "251") (name "unconnected-(R-Pad57)") (class "Default")
      (node (ref "R") (pin "57") (pinfunction "57_57") (pintype "passive"))
    )
    (net (code "252") (name "unconnected-(R-Pad58)") (class "Default")
      (node (ref "R") (pin "58") (pinfunction "58_58") (pintype "passive"))
    )
    (net (code "253") (name "unconnected-(R-Pad59)") (class "Default")
      (node (ref "R") (pin "59") (pinfunction "59_59") (pintype "passive"))
    )
    (net (code "254") (name "unconnected-(R-Pad60)") (class "Default")
      (node (ref "R") (pin "60") (pinfunction "60_60") (pintype "passive"))
    )
    (net (code "255") (name "unconnected-(U5-EN-Pad5)") (class "Default")
      (node (ref "U5") (pin "5") (pinfunction "EN_5") (pintype "passive+no_connect"))
    )
    (net (code "256") (name "unconnected-(U5-NC-Pad2)") (class "Default")
      (node (ref "U5") (pin "2") (pinfunction "NC_2") (pintype "passive"))
    )
    (net (code "257") (name "unconnected-(U5-NC-Pad3)") (class "Default")
      (node (ref "U5") (pin "3") (pinfunction "NC_3") (pintype "passive"))
    )
    (net (code "258") (name "unconnected-(USBA-D+-Pad3)") (class "Default")
      (node (ref "USBA") (pin "3") (pinfunction "D+_3") (pintype "passive+no_connect"))
    )
    (net (code "259") (name "unconnected-(USBA-D--Pad2)") (class "Default")
      (node (ref "USBA") (pin "2") (pinfunction "D-_2") (pintype "passive+no_connect"))
    )
  )
)
